# Sheet1.net
KiCad netlist of a schematic drawn in Altium Designer
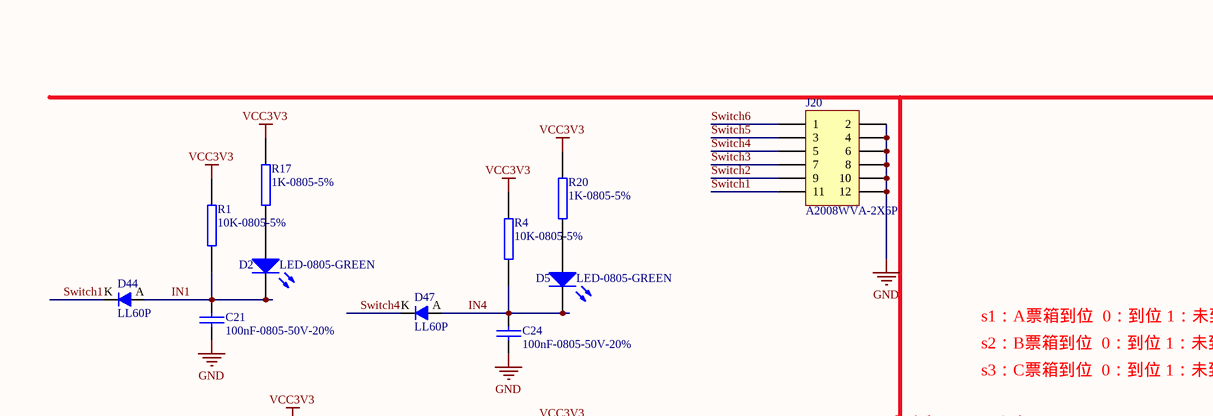
[diagram p0: Sheet1.SchDoc, top left]
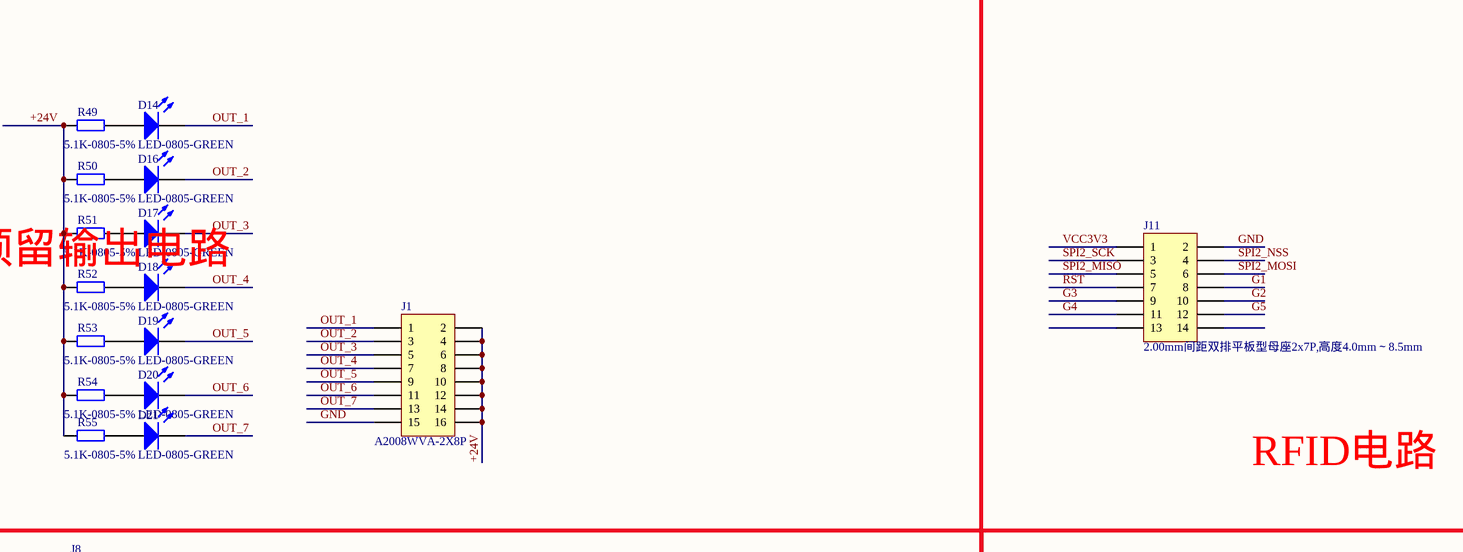
[diagram p1: Sheet1.SchDoc, top middle]
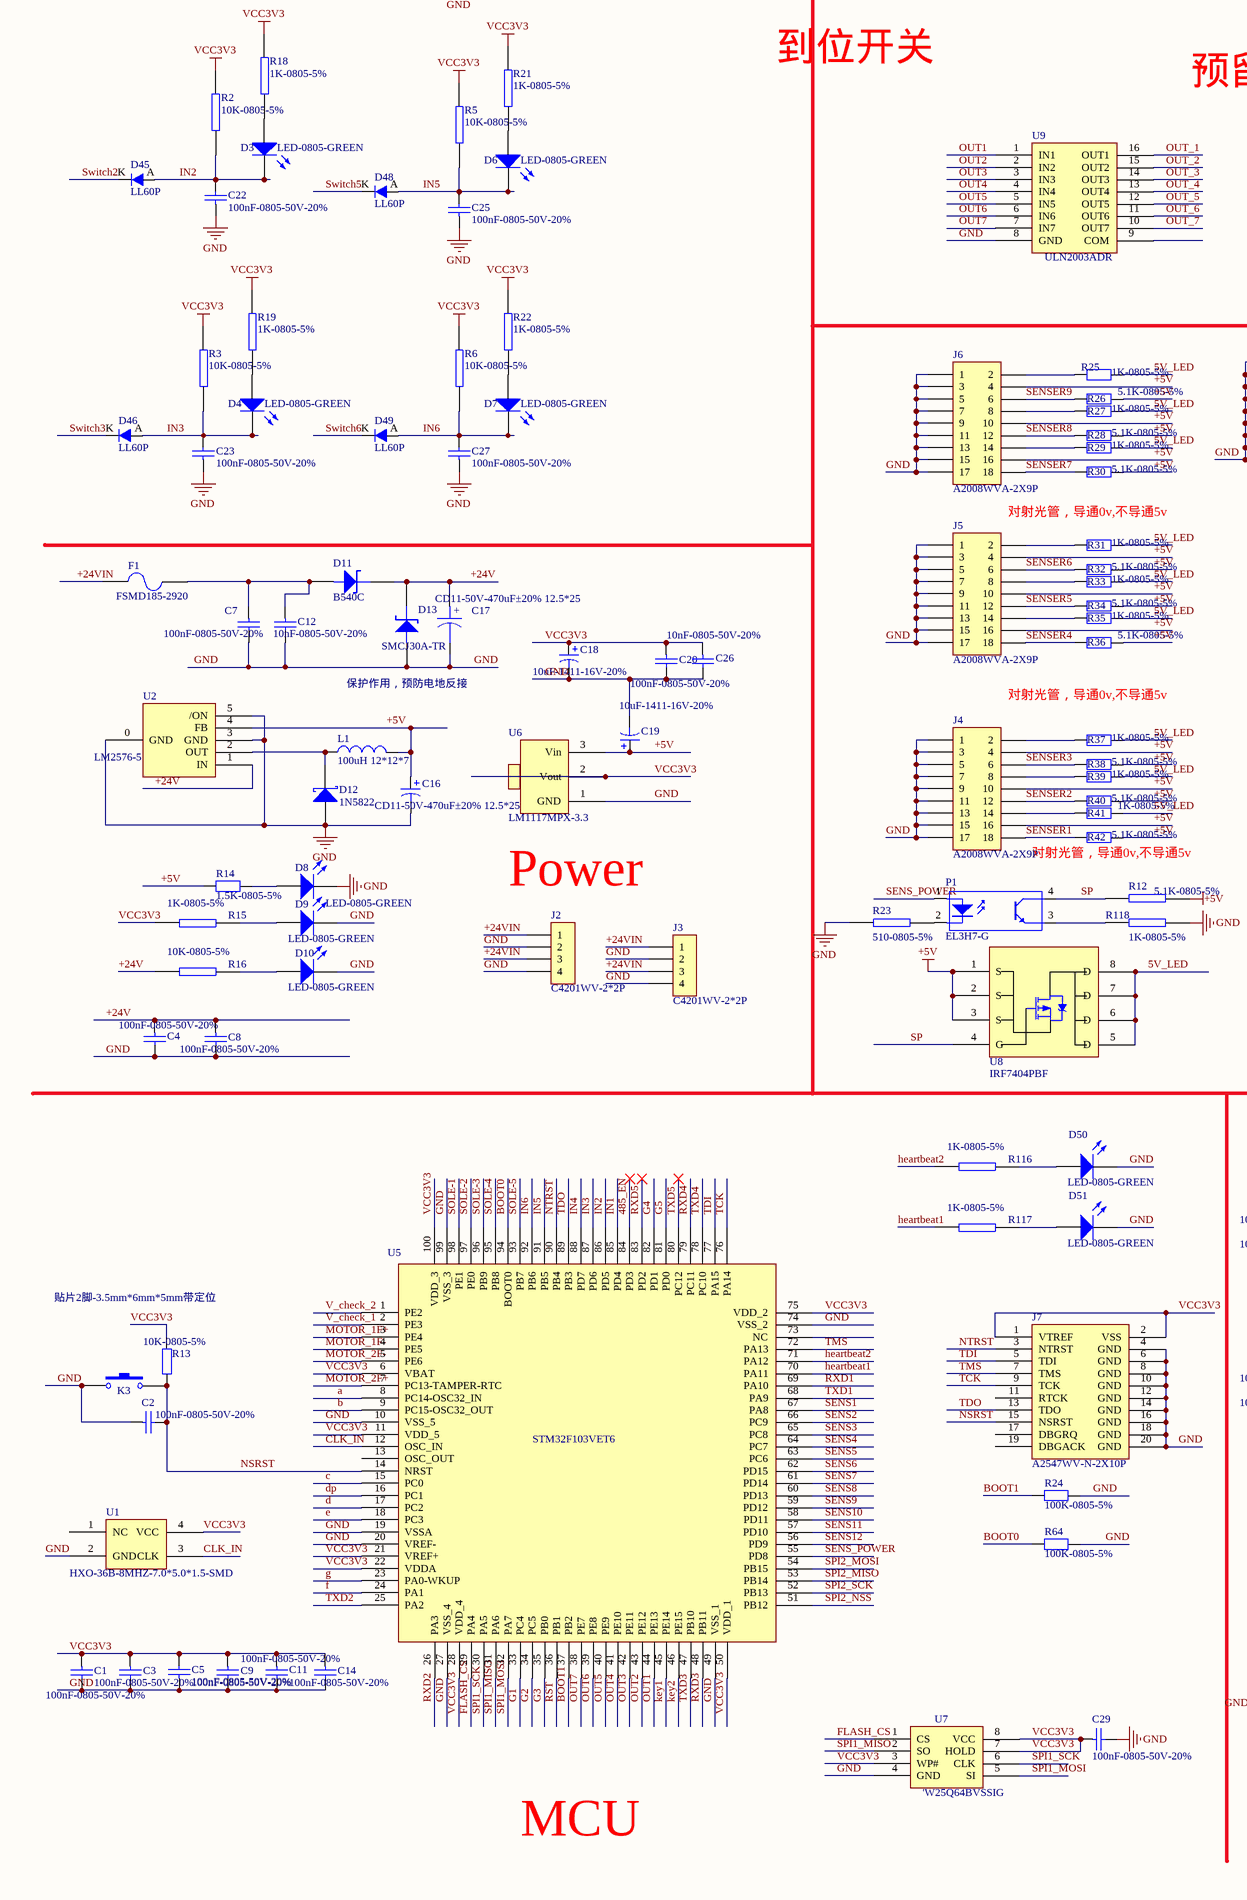
[diagram p2: Sheet1.SchDoc, bottom left]
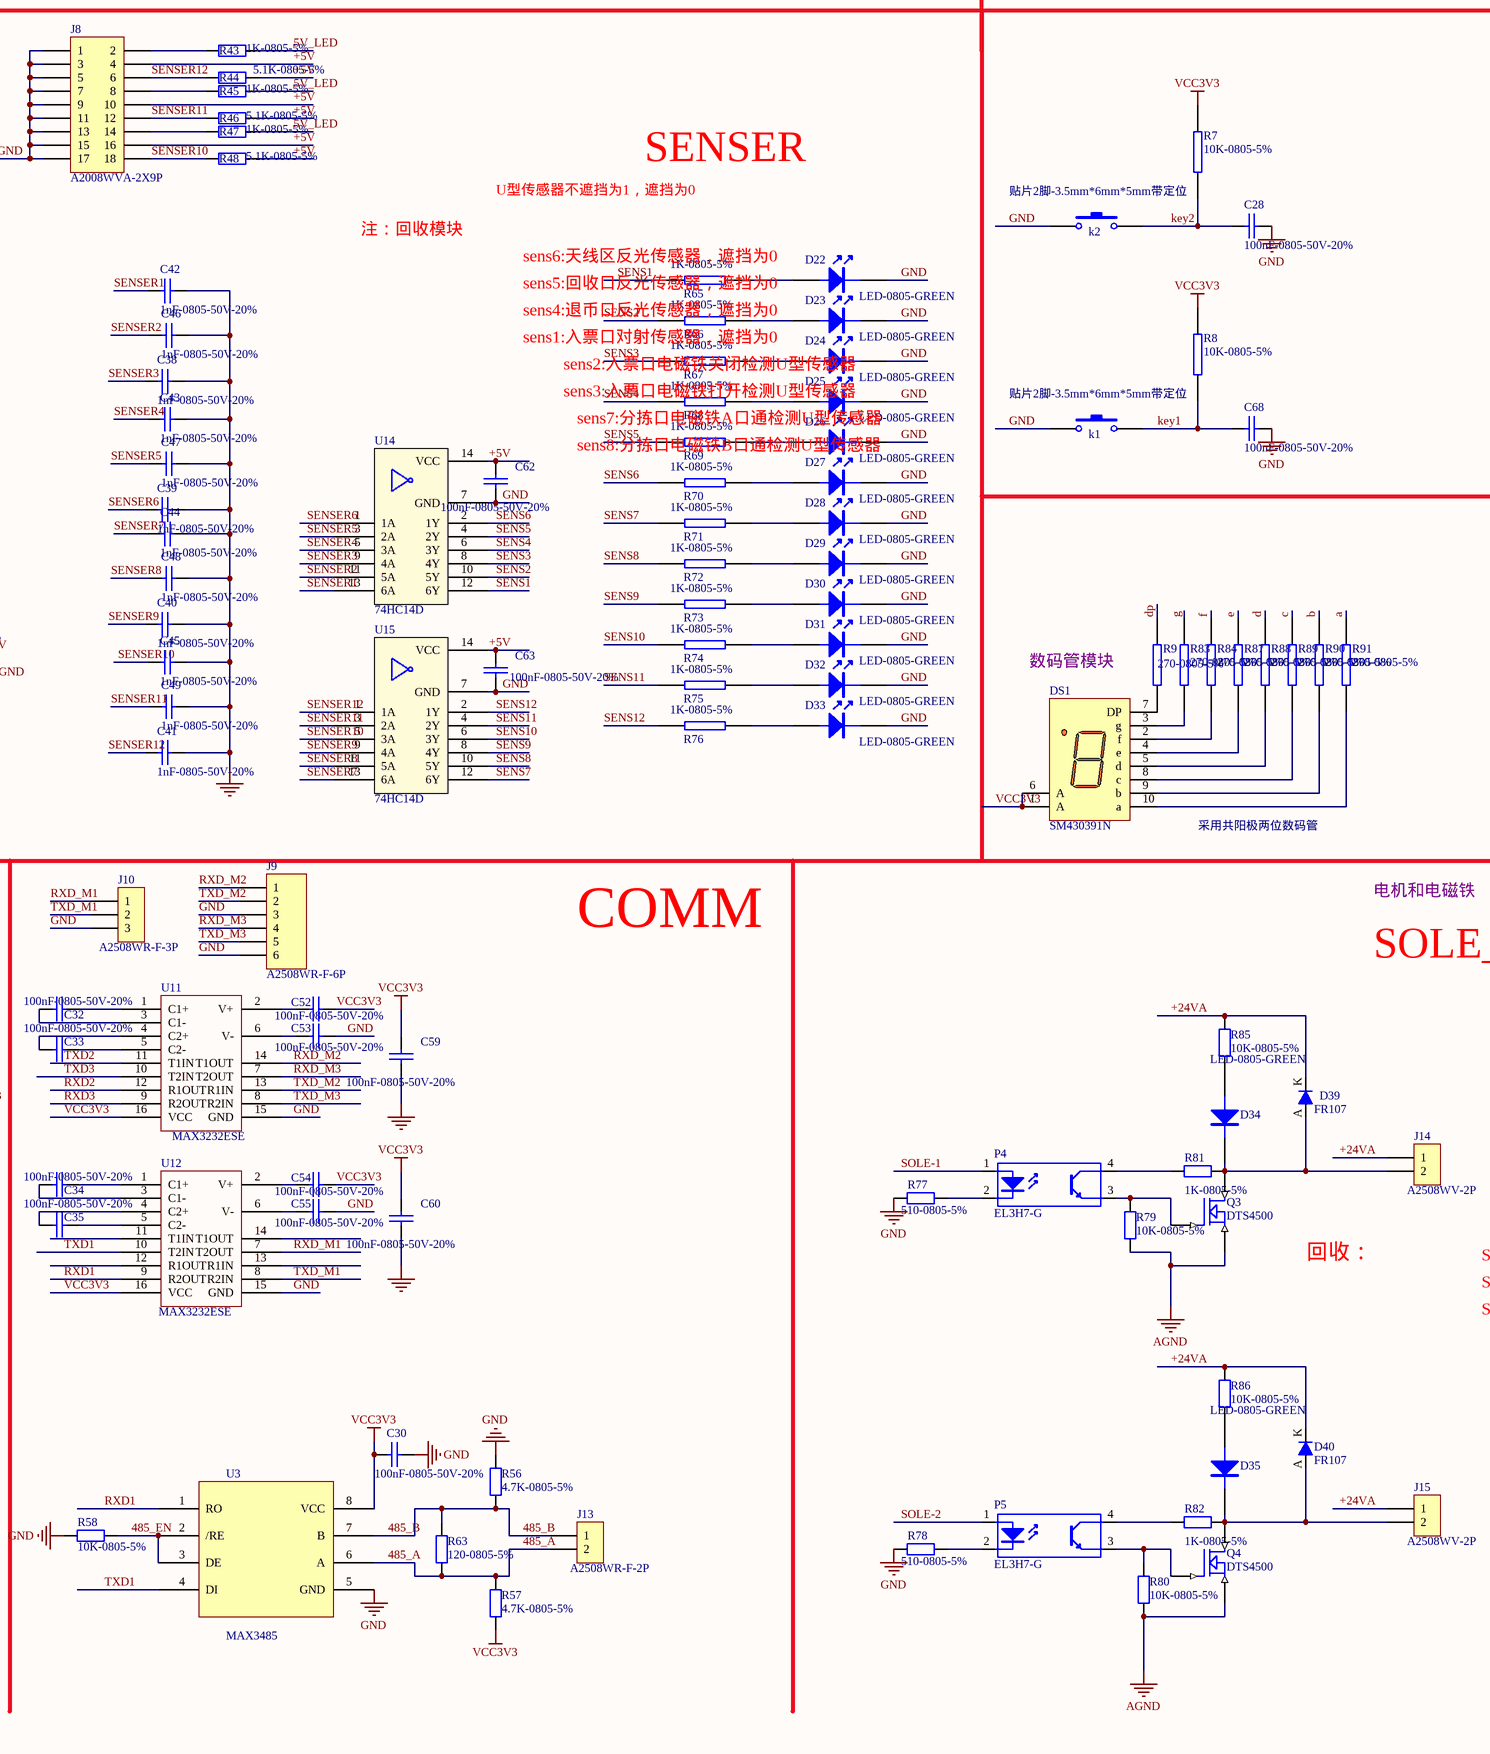
[diagram p3: Sheet1.SchDoc, bottom middle]
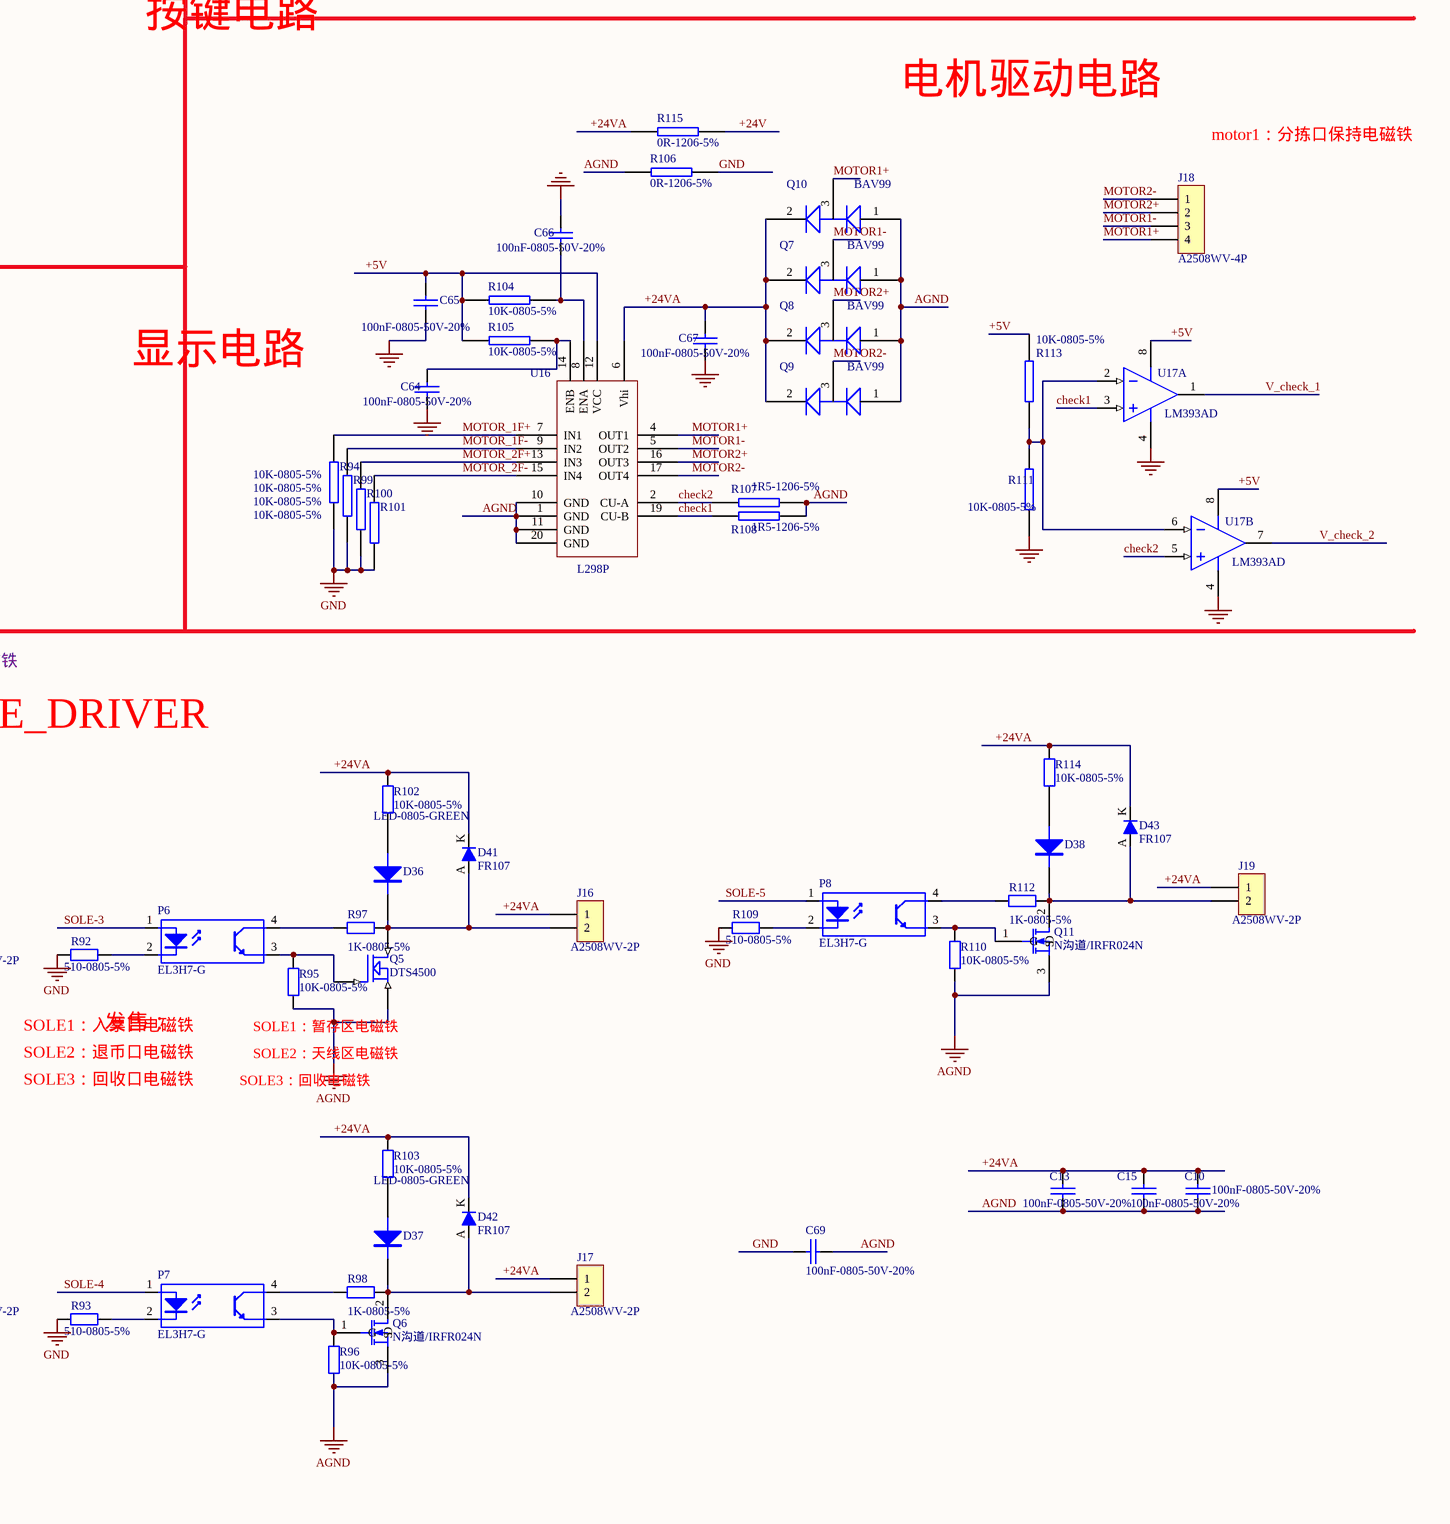
[diagram p4: Sheet1.SchDoc, bottom right]

(export (version "E")
  (design (tool "Eeschema 10.0.6"))
  (components
    (comp (ref "C1")
      (value "100nF-0805-50V-20%")
      (footprint "0805")
      (description "Capacitor")
      (libsource (lib "*") (part "CAP"))
    )
    (comp (ref "C2")
      (value "100nF-0805-50V-20%")
      (footprint "0805")
      (description "Capacitor")
      (libsource (lib "*") (part "CAP"))
    )
    (comp (ref "C3")
      (value "100nF-0805-50V-20%")
      (footprint "0805")
      (description "Capacitor")
      (libsource (lib "*") (part "CAP"))
    )
    (comp (ref "C4")
      (value "100nF-0805-50V-20%")
      (footprint "0805")
      (description "Capacitor")
      (libsource (lib "*") (part "CAP"))
    )
    (comp (ref "C5")
      (value "100nF-0805-50V-20%")
      (footprint "0805")
      (description "Capacitor")
      (libsource (lib "*") (part "CAP"))
    )
    (comp (ref "C7")
      (value "100nF-0805-50V-20%")
      (footprint "0805")
      (description "Capacitor")
      (libsource (lib "*") (part "CAP"))
    )
    (comp (ref "C8")
      (value "100nF-0805-50V-20%")
      (footprint "0805")
      (description "Capacitor")
      (libsource (lib "*") (part "CAP"))
    )
    (comp (ref "C9")
      (value "100nF-0805-50V-20%")
      (footprint "0805")
      (description "Capacitor")
      (libsource (lib "*") (part "CAP"))
    )
    (comp (ref "C10")
      (value "100nF-0805-50V-20%")
      (footprint "0805")
      (description "Capacitor")
      (libsource (lib "*") (part "CAP"))
    )
    (comp (ref "C11")
      (value "100nF-0805-50V-20%")
      (footprint "0805")
      (description "Capacitor")
      (libsource (lib "*") (part "CAP"))
    )
    (comp (ref "C12")
      (value "10nF-0805-50V-20%")
      (footprint "0805")
      (description "Capacitor")
      (libsource (lib "*") (part "CAP"))
    )
    (comp (ref "C13")
      (value "100nF-0805-50V-20%")
      (footprint "0805")
      (description "Capacitor")
      (libsource (lib "*") (part "CAP"))
    )
    (comp (ref "C14")
      (value "100nF-0805-50V-20%")
      (footprint "0805")
      (description "Capacitor")
      (libsource (lib "*") (part "CAP"))
    )
    (comp (ref "C15")
      (value "100nF-0805-50V-20%")
      (footprint "0805")
      (description "Capacitor")
      (libsource (lib "*") (part "CAP"))
    )
    (comp (ref "C16")
      (value "CD11-50V-470uF±20% 12.5*25")
      (footprint "RB.2/.4")
      (description "Polarized Capacitor (Radial)")
      (fields (field (name "PUBLISHER") "Altium Limited"))
      (libsource (lib "Miscellaneous Devices") (part "Cap Pol1"))
    )
    (comp (ref "C17")
      (value "CD11-50V-470uF±20% 12.5*25")
      (footprint "RB.2/.4")
      (description "Capacitor")
      (libsource (lib "*") (part "CAPACITOR POL"))
    )
    (comp (ref "C18")
      (value "10uF-1411-16V-20%")
      (footprint "1411-B")
      (description "Polarized Capacitor (Radial)")
      (fields (field (name "PUBLISHER") "Altium Limited"))
      (libsource (lib "Miscellaneous Devices") (part "Cap Pol1"))
    )
    (comp (ref "C19")
      (value "10uF-1411-16V-20%")
      (footprint "1411-B")
      (description "Polarized Capacitor (Radial)")
      (fields (field (name "PUBLISHER") "Altium Limited"))
      (libsource (lib "Miscellaneous Devices") (part "Cap Pol1"))
    )
    (comp (ref "C20")
      (value "100nF-0805-50V-20%")
      (footprint "0805")
      (description "Capacitor")
      (libsource (lib "*") (part "CAP"))
    )
    (comp (ref "C21")
      (value "100nF-0805-50V-20%")
      (footprint "0805")
      (description "Capacitor")
      (libsource (lib "*") (part "CAP"))
    )
    (comp (ref "C22")
      (value "100nF-0805-50V-20%")
      (footprint "0805")
      (description "Capacitor")
      (libsource (lib "*") (part "CAP"))
    )
    (comp (ref "C23")
      (value "100nF-0805-50V-20%")
      (footprint "0805")
      (description "Capacitor")
      (libsource (lib "*") (part "CAP"))
    )
    (comp (ref "C24")
      (value "100nF-0805-50V-20%")
      (footprint "0805")
      (description "Capacitor")
      (libsource (lib "*") (part "CAP"))
    )
    (comp (ref "C25")
      (value "100nF-0805-50V-20%")
      (footprint "0805")
      (description "Capacitor")
      (libsource (lib "*") (part "CAP"))
    )
    (comp (ref "C26")
      (value "10nF-0805-50V-20%")
      (footprint "0805")
      (description "Capacitor")
      (libsource (lib "*") (part "CAP"))
    )
    (comp (ref "C27")
      (value "100nF-0805-50V-20%")
      (footprint "0805")
      (description "Capacitor")
      (libsource (lib "*") (part "CAP"))
    )
    (comp (ref "C28")
      (value "100nF-0805-50V-20%")
      (footprint "0805")
      (description "Capacitor")
      (libsource (lib "*") (part "CAP"))
    )
    (comp (ref "C29")
      (value "100nF-0805-50V-20%")
      (footprint "0805")
      (description "Capacitor")
      (libsource (lib "*") (part "CAP"))
    )
    (comp (ref "C30")
      (value "100nF-0805-50V-20%")
      (footprint "0805")
      (description "Capacitor")
      (libsource (lib "*") (part "CAP"))
    )
    (comp (ref "C32")
      (value "100nF-0805-50V-20%")
      (footprint "0805")
      (description "Capacitor")
      (libsource (lib "") (part "CAP_1"))
    )
    (comp (ref "C33")
      (value "100nF-0805-50V-20%")
      (footprint "0805")
      (description "Capacitor")
      (libsource (lib "") (part "CAP_1"))
    )
    (comp (ref "C34")
      (value "100nF-0805-50V-20%")
      (footprint "0805")
      (description "Capacitor")
      (libsource (lib "") (part "CAP_1"))
    )
    (comp (ref "C35")
      (value "100nF-0805-50V-20%")
      (footprint "0805")
      (description "Capacitor")
      (libsource (lib "") (part "CAP_1"))
    )
    (comp (ref "C38")
      (value "1nF-0805-50V-20%")
      (footprint "0805")
      (description "Capacitor")
      (libsource (lib "*") (part "CAP"))
    )
    (comp (ref "C39")
      (value "1nF-0805-50V-20%")
      (footprint "0805")
      (description "Capacitor")
      (libsource (lib "*") (part "CAP"))
    )
    (comp (ref "C40")
      (value "1nF-0805-50V-20%")
      (footprint "0805")
      (description "Capacitor")
      (libsource (lib "*") (part "CAP"))
    )
    (comp (ref "C41")
      (value "1nF-0805-50V-20%")
      (footprint "0805")
      (description "Capacitor")
      (libsource (lib "*") (part "CAP"))
    )
    (comp (ref "C42")
      (value "1nF-0805-50V-20%")
      (footprint "0805")
      (description "Capacitor")
      (libsource (lib "*") (part "CAP"))
    )
    (comp (ref "C43")
      (value "1nF-0805-50V-20%")
      (footprint "0805")
      (description "Capacitor")
      (libsource (lib "*") (part "CAP"))
    )
    (comp (ref "C44")
      (value "1nF-0805-50V-20%")
      (footprint "0805")
      (description "Capacitor")
      (libsource (lib "*") (part "CAP"))
    )
    (comp (ref "C45")
      (value "1nF-0805-50V-20%")
      (footprint "0805")
      (description "Capacitor")
      (libsource (lib "*") (part "CAP"))
    )
    (comp (ref "C46")
      (value "1nF-0805-50V-20%")
      (footprint "0805")
      (description "Capacitor")
      (libsource (lib "*") (part "CAP"))
    )
    (comp (ref "C47")
      (value "1nF-0805-50V-20%")
      (footprint "0805")
      (description "Capacitor")
      (libsource (lib "*") (part "CAP"))
    )
    (comp (ref "C48")
      (value "1nF-0805-50V-20%")
      (footprint "0805")
      (description "Capacitor")
      (libsource (lib "*") (part "CAP"))
    )
    (comp (ref "C49")
      (value "1nF-0805-50V-20%")
      (footprint "0805")
      (description "Capacitor")
      (libsource (lib "*") (part "CAP"))
    )
    (comp (ref "C52")
      (value "100nF-0805-50V-20%")
      (footprint "0805")
      (description "Capacitor")
      (libsource (lib "") (part "CAP_1"))
    )
    (comp (ref "C53")
      (value "100nF-0805-50V-20%")
      (footprint "0805")
      (description "Capacitor")
      (libsource (lib "") (part "CAP_1"))
    )
    (comp (ref "C54")
      (value "100nF-0805-50V-20%")
      (footprint "0805")
      (description "Capacitor")
      (libsource (lib "") (part "CAP_1"))
    )
    (comp (ref "C55")
      (value "100nF-0805-50V-20%")
      (footprint "0805")
      (description "Capacitor")
      (libsource (lib "") (part "CAP_1"))
    )
    (comp (ref "C59")
      (value "100nF-0805-50V-20%")
      (footprint "0805")
      (description "Capacitor")
      (libsource (lib "*") (part "CAP"))
    )
    (comp (ref "C60")
      (value "100nF-0805-50V-20%")
      (footprint "0805")
      (description "Capacitor")
      (libsource (lib "*") (part "CAP"))
    )
    (comp (ref "C62")
      (value "100nF-0805-50V-20%")
      (footprint "0805")
      (description "Capacitor")
      (libsource (lib "*") (part "CAP"))
    )
    (comp (ref "C63")
      (value "100nF-0805-50V-20%")
      (footprint "0805")
      (description "Capacitor")
      (libsource (lib "*") (part "CAP"))
    )
    (comp (ref "C64")
      (value "100nF-0805-50V-20%")
      (footprint "0805")
      (description "Capacitor")
      (libsource (lib "*") (part "CAP"))
    )
    (comp (ref "C65")
      (value "100nF-0805-50V-20%")
      (footprint "0805")
      (description "Capacitor")
      (libsource (lib "*") (part "CAP"))
    )
    (comp (ref "C66")
      (value "100nF-0805-50V-20%")
      (footprint "0805")
      (description "Capacitor")
      (libsource (lib "*") (part "CAP"))
    )
    (comp (ref "C67")
      (value "100nF-0805-50V-20%")
      (footprint "0805")
      (description "Capacitor")
      (libsource (lib "*") (part "CAP"))
    )
    (comp (ref "C68")
      (value "100nF-0805-50V-20%")
      (footprint "0805")
      (description "Capacitor")
      (libsource (lib "*") (part "CAP"))
    )
    (comp (ref "C69")
      (value "100nF-0805-50V-20%")
      (footprint "0805")
      (description "Capacitor")
      (libsource (lib "*") (part "CAP"))
    )
    (comp (ref "D2")
      (value "LED-0805-GREEN")
      (footprint "LED-0805")
      (description "Typical INFRARED GaAs LED")
      (fields (field (name "PUBLISHER") "Altium Limited"))
      (libsource (lib "Miscellaneous Devices") (part "LED0"))
    )
    (comp (ref "D3")
      (value "LED-0805-GREEN")
      (footprint "LED-0805")
      (description "Typical INFRARED GaAs LED")
      (fields (field (name "PUBLISHER") "Altium Limited"))
      (libsource (lib "Miscellaneous Devices") (part "LED0"))
    )
    (comp (ref "D4")
      (value "LED-0805-GREEN")
      (footprint "LED-0805")
      (description "Typical INFRARED GaAs LED")
      (fields (field (name "PUBLISHER") "Altium Limited"))
      (libsource (lib "Miscellaneous Devices") (part "LED0"))
    )
    (comp (ref "D5")
      (value "LED-0805-GREEN")
      (footprint "LED-0805")
      (description "Typical INFRARED GaAs LED")
      (fields (field (name "PUBLISHER") "Altium Limited"))
      (libsource (lib "Miscellaneous Devices") (part "LED0"))
    )
    (comp (ref "D6")
      (value "LED-0805-GREEN")
      (footprint "LED-0805")
      (description "Typical INFRARED GaAs LED")
      (fields (field (name "PUBLISHER") "Altium Limited"))
      (libsource (lib "Miscellaneous Devices") (part "LED0"))
    )
    (comp (ref "D7")
      (value "LED-0805-GREEN")
      (footprint "LED-0805")
      (description "Typical INFRARED GaAs LED")
      (fields (field (name "PUBLISHER") "Altium Limited"))
      (libsource (lib "Miscellaneous Devices") (part "LED0"))
    )
    (comp (ref "D8")
      (value "LED-0805-GREEN")
      (footprint "LED-0805")
      (description "Typical INFRARED GaAs LED")
      (fields (field (name "PUBLISHER") "Altium Limited"))
      (libsource (lib "Miscellaneous Devices") (part "LED0"))
    )
    (comp (ref "D9")
      (value "LED-0805-GREEN")
      (footprint "LED-0805")
      (description "Typical INFRARED GaAs LED")
      (fields (field (name "PUBLISHER") "Altium Limited"))
      (libsource (lib "Miscellaneous Devices") (part "LED0"))
    )
    (comp (ref "D10")
      (value "LED-0805-GREEN")
      (footprint "LED-0805")
      (description "Typical INFRARED GaAs LED")
      (fields (field (name "PUBLISHER") "Altium Limited"))
      (libsource (lib "Miscellaneous Devices") (part "LED0"))
    )
    (comp (ref "D11")
      (value "B540C")
      (footprint "SMC")
      (description "Zener Diode")
      (libsource (lib "*") (part "ZENER2"))
    )
    (comp (ref "D12")
      (value "1N5822")
      (footprint "IN5822 SMT")
      (description "Schottky Diode")
      (fields (field (name "PUBLISHER") "Altium Limited"))
      (libsource (lib "Miscellaneous Devices") (part "D Schottky"))
    )
    (comp (ref "D13")
      (value "SMCJ30A-TR")
      (footprint "SMC")
      (description "Zener Diode")
      (libsource (lib "*") (part "ZENER2"))
    )
    (comp (ref "D14")
      (value "LED-0805-GREEN")
      (footprint "LED-0805")
      (description "Typical INFRARED GaAs LED")
      (fields (field (name "PUBLISHER") "Altium Limited"))
      (libsource (lib "Miscellaneous Devices") (part "LED0"))
    )
    (comp (ref "D16")
      (value "LED-0805-GREEN")
      (footprint "LED-0805")
      (description "Typical INFRARED GaAs LED")
      (fields (field (name "PUBLISHER") "Altium Limited"))
      (libsource (lib "Miscellaneous Devices") (part "LED0"))
    )
    (comp (ref "D17")
      (value "LED-0805-GREEN")
      (footprint "LED-0805")
      (description "Typical INFRARED GaAs LED")
      (fields (field (name "PUBLISHER") "Altium Limited"))
      (libsource (lib "Miscellaneous Devices") (part "LED0"))
    )
    (comp (ref "D18")
      (value "LED-0805-GREEN")
      (footprint "LED-0805")
      (description "Typical INFRARED GaAs LED")
      (fields (field (name "PUBLISHER") "Altium Limited"))
      (libsource (lib "Miscellaneous Devices") (part "LED0"))
    )
    (comp (ref "D19")
      (value "LED-0805-GREEN")
      (footprint "LED-0805")
      (description "Typical INFRARED GaAs LED")
      (fields (field (name "PUBLISHER") "Altium Limited"))
      (libsource (lib "Miscellaneous Devices") (part "LED0"))
    )
    (comp (ref "D20")
      (value "LED-0805-GREEN")
      (footprint "LED-0805")
      (description "Typical INFRARED GaAs LED")
      (fields (field (name "PUBLISHER") "Altium Limited"))
      (libsource (lib "Miscellaneous Devices") (part "LED0"))
    )
    (comp (ref "D21")
      (value "LED-0805-GREEN")
      (footprint "LED-0805")
      (description "Typical INFRARED GaAs LED")
      (fields (field (name "PUBLISHER") "Altium Limited"))
      (libsource (lib "Miscellaneous Devices") (part "LED0"))
    )
    (comp (ref "D22") (value "LED-0805-GREEN") (footprint "LED-0805") (libsource (lib "*") (part "LED")))
    (comp (ref "D23") (value "LED-0805-GREEN") (footprint "LED-0805") (libsource (lib "*") (part "LED")))
    (comp (ref "D24") (value "LED-0805-GREEN") (footprint "LED-0805") (libsource (lib "*") (part "LED")))
    (comp (ref "D25") (value "LED-0805-GREEN") (footprint "LED-0805") (libsource (lib "*") (part "LED")))
    (comp (ref "D26") (value "LED-0805-GREEN") (footprint "LED-0805") (libsource (lib "*") (part "LED")))
    (comp (ref "D27") (value "LED-0805-GREEN") (footprint "LED-0805") (libsource (lib "*") (part "LED")))
    (comp (ref "D28") (value "LED-0805-GREEN") (footprint "LED-0805") (libsource (lib "*") (part "LED")))
    (comp (ref "D29") (value "LED-0805-GREEN") (footprint "LED-0805") (libsource (lib "*") (part "LED")))
    (comp (ref "D30") (value "LED-0805-GREEN") (footprint "LED-0805") (libsource (lib "*") (part "LED")))
    (comp (ref "D31") (value "LED-0805-GREEN") (footprint "LED-0805") (libsource (lib "*") (part "LED")))
    (comp (ref "D32") (value "LED-0805-GREEN") (footprint "LED-0805") (libsource (lib "*") (part "LED")))
    (comp (ref "D33") (value "LED-0805-GREEN") (footprint "LED-0805") (libsource (lib "*") (part "LED")))
    (comp (ref "D34")
      (value "LED-0805-GREEN")
      (footprint "LED-0805")
      (description "Diode")
      (libsource (lib "*") (part "DIODE"))
    )
    (comp (ref "D35")
      (value "LED-0805-GREEN")
      (footprint "LED-0805")
      (description "Diode")
      (libsource (lib "*") (part "DIODE"))
    )
    (comp (ref "D36")
      (value "LED-0805-GREEN")
      (footprint "LED-0805")
      (description "Diode")
      (libsource (lib "*") (part "DIODE"))
    )
    (comp (ref "D37")
      (value "LED-0805-GREEN")
      (footprint "LED-0805")
      (description "Diode")
      (libsource (lib "*") (part "DIODE"))
    )
    (comp (ref "D38")
      (value "LED-0805-GREEN")
      (footprint "LED-0805")
      (description "Diode")
      (libsource (lib "*") (part "DIODE"))
    )
    (comp (ref "D39")
      (value "FR107")
      (footprint "DO-214AC")
      (libsource (lib "T-SZLG-MCB-16-0247-PN-37990042-SZLG-Hopper-01控制板") (part "1N4148"))
    )
    (comp (ref "D40")
      (value "FR107")
      (footprint "DO-214AC")
      (libsource (lib "T-SZLG-MCB-16-0247-PN-37990042-SZLG-Hopper-01控制板") (part "1N4148"))
    )
    (comp (ref "D41")
      (value "FR107")
      (footprint "DO-214AC")
      (libsource (lib "T-SZLG-MCB-16-0247-PN-37990042-SZLG-Hopper-01控制板") (part "1N4148"))
    )
    (comp (ref "D42")
      (value "FR107")
      (footprint "DO-214AC")
      (libsource (lib "T-SZLG-MCB-16-0247-PN-37990042-SZLG-Hopper-01控制板") (part "1N4148"))
    )
    (comp (ref "D43")
      (value "FR107")
      (footprint "DO-214AC")
      (libsource (lib "T-SZLG-MCB-16-0247-PN-37990042-SZLG-Hopper-01控制板") (part "1N4148"))
    )
    (comp (ref "D44")
      (value "LL60P")
      (footprint "PCB22:DIODE")
      (libsource (lib "T-SZLG-MCB-16-0247-PN-37990042-SZLG-Hopper-01控制板") (part "1N4148"))
    )
    (comp (ref "D45")
      (value "LL60P")
      (footprint "DIODE")
      (libsource (lib "T-SZLG-MCB-16-0247-PN-37990042-SZLG-Hopper-01控制板") (part "1N4148"))
    )
    (comp (ref "D46")
      (value "LL60P")
      (footprint "DIODE")
      (libsource (lib "T-SZLG-MCB-16-0247-PN-37990042-SZLG-Hopper-01控制板") (part "1N4148"))
    )
    (comp (ref "D47")
      (value "LL60P")
      (footprint "DIODE")
      (libsource (lib "T-SZLG-MCB-16-0247-PN-37990042-SZLG-Hopper-01控制板") (part "1N4148"))
    )
    (comp (ref "D48")
      (value "LL60P")
      (footprint "DIODE")
      (libsource (lib "T-SZLG-MCB-16-0247-PN-37990042-SZLG-Hopper-01控制板") (part "1N4148"))
    )
    (comp (ref "D49")
      (value "LL60P")
      (footprint "DIODE")
      (libsource (lib "T-SZLG-MCB-16-0247-PN-37990042-SZLG-Hopper-01控制板") (part "1N4148"))
    )
    (comp (ref "D50")
      (value "LED-0805-GREEN")
      (footprint "LED-0805")
      (description "Typical INFRARED GaAs LED")
      (fields (field (name "PUBLISHER") "Altium Limited"))
      (libsource (lib "Miscellaneous Devices") (part "LED0"))
    )
    (comp (ref "D51")
      (value "LED-0805-GREEN")
      (footprint "LED-0805")
      (description "Typical INFRARED GaAs LED")
      (fields (field (name "PUBLISHER") "Altium Limited"))
      (libsource (lib "Miscellaneous Devices") (part "LED0"))
    )
    (comp (ref "DS1")
      (value "SM430391N")
      (footprint "LEDDIP-10")
      (description "7.62 mm Black Surface Orange 7-Segment Display: CA, RH DP")
      (fields (field (name "PUBLISHER") "Altium Limited"))
      (libsource (lib "*") (part "Dpy Amber-CA"))
    )
    (comp (ref "F1")
      (value "FSMD185-2920")
      (footprint "2920")
      (description "Fuse")
      (libsource (lib "*") (part "FUSE2"))
    )
    (comp (ref "J1")
      (value "A2008WVA-2X8P")
      (footprint "PCB12:A2008WVA-2X8P")
      (description "Header, 8-Pin, Dual row")
      (fields (field (name "PUBLISHER") "Altium Limited"))
      (libsource (lib "Miscellaneous Connectors") (part "Header 8X2"))
    )
    (comp (ref "J2")
      (value "C4201WV-2*2P")
      (footprint "MX4 .2- 2*2P-180")
      (description "Connector")
      (libsource (lib "*") (part "CON4"))
    )
    (comp (ref "J3")
      (value "C4201WV-2*2P")
      (footprint "PCB1:MX4 .2- 2*2P-180")
      (description "Connector")
      (libsource (lib "*") (part "CON4"))
    )
    (comp (ref "J4")
      (value "A2008WVA-2X9P")
      (footprint "PCB12:A2008WVA-2X9P")
      (description "Header, 9-Pin, Dual row")
      (fields (field (name "PUBLISHER") "Altium Limited"))
      (libsource (lib "Miscellaneous Connectors") (part "Header 9X2"))
    )
    (comp (ref "J5")
      (value "A2008WVA-2X9P")
      (footprint "PCB12:A2008WVA-2X9P")
      (description "Header, 9-Pin, Dual row")
      (fields (field (name "PUBLISHER") "Altium Limited"))
      (libsource (lib "Miscellaneous Connectors") (part "Header 9X2"))
    )
    (comp (ref "J6")
      (value "A2008WVA-2X9P")
      (footprint "PCB12:A2008WVA-2X9P")
      (description "Header, 9-Pin, Dual row")
      (fields (field (name "PUBLISHER") "Altium Limited"))
      (libsource (lib "Miscellaneous Connectors") (part "Header 9X2"))
    )
    (comp (ref "J7") (value "A2547WV-N-2X10P") (footprint "JTAG_20") (libsource (lib "STM32") (part "JTAG")))
    (comp (ref "J8")
      (value "A2008WVA-2X9P")
      (footprint "PCB12:A2008WVA-2X9P")
      (description "Header, 9-Pin, Dual row")
      (fields (field (name "PUBLISHER") "Altium Limited"))
      (libsource (lib "Miscellaneous Connectors") (part "Header 9X2"))
    )
    (comp (ref "J9")
      (value "A2508WR-F-6P")
      (footprint "PCB1:2.5-6P  90 JXT")
      (description "Header, 6-Pin")
      (fields (field (name "PUBLISHER") "Altium Limited"))
      (libsource (lib "Miscellaneous Connectors") (part "Header 6"))
    )
    (comp (ref "J10")
      (value "A2508WR-F-3P")
      (footprint "PCB1:2.5-3P  90 JXT")
      (description "Connector")
      (libsource (lib "*") (part "CON3"))
    )
    (comp (ref "J11")
      (value "2.00mm间距双排平板型母座2x7P,高度4.0mm～8.5mm")
      (footprint "PCB1:IDC14-2.0-F")
      (description "Header, 7-Pin, Dual row, Right Angle")
      (fields (field (name "PUBLISHER") "Altium Limited"))
      (libsource (lib "Miscellaneous Connectors") (part "Header 7X2H"))
    )
    (comp (ref "J13")
      (value "A2508WR-F-2P")
      (footprint "2.5-2P  90 JXT")
      (libsource (lib "元件库") (part "CON2"))
    )
    (comp (ref "J14")
      (value "A2508WV-2P")
      (footprint "2.5-2P  180 JXT")
      (libsource (lib "元件库") (part "CON2"))
    )
    (comp (ref "J15")
      (value "A2508WV-2P")
      (footprint "2.5-2P  180 JXT")
      (libsource (lib "元件库") (part "CON2"))
    )
    (comp (ref "J16")
      (value "A2508WV-2P")
      (footprint "2.5-2P  180 JXT")
      (libsource (lib "元件库") (part "CON2"))
    )
    (comp (ref "J17")
      (value "A2508WV-2P")
      (footprint "2.5-2P  180 JXT")
      (libsource (lib "元件库") (part "CON2"))
    )
    (comp (ref "J18")
      (value "A2508WV-4P")
      (footprint "W143-4")
      (description "Connector")
      (libsource (lib "*") (part "CON4"))
    )
    (comp (ref "J19")
      (value "A2508WV-2P")
      (footprint "2.5-2P  180 JXT")
      (libsource (lib "元件库") (part "CON2"))
    )
    (comp (ref "J20")
      (value "A2008WVA-2X6P")
      (footprint "PCB12:A2008WVA-2X6P")
      (description "Header, 6-Pin, Dual row")
      (fields (field (name "PUBLISHER") "Altium Limited"))
      (libsource (lib "Miscellaneous Connectors") (part "Header 6X2"))
    )
    (comp (ref "k1")
      (value "贴片2脚-3.5mm*6mm*5mm带定位")
      (footprint "BUTTON2")
      (description "Switch")
      (libsource (lib "SilvestStandardSchLib") (part "Switch"))
    )
    (comp (ref "k2")
      (value "贴片2脚-3.5mm*6mm*5mm带定位")
      (footprint "BUTTON2")
      (description "Switch")
      (libsource (lib "SilvestStandardSchLib") (part "Switch"))
    )
    (comp (ref "K3")
      (value "贴片2脚-3.5mm*6mm*5mm带定位")
      (footprint "BUTTON2")
      (description "Switch")
      (libsource (lib "SilvestStandardSchLib") (part "Switch"))
    )
    (comp (ref "L1")
      (value "100uH 12*12*7")
      (footprint "Inductor SMT7")
      (description "Inductor")
      (fields (field (name "PUBLISHER") "Altium Limited"))
      (libsource (lib "Miscellaneous Devices") (part "Inductor"))
    )
    (comp (ref "P1")
      (value "EL3H7-G")
      (footprint "SSOP4")
      (description "OpticalCoupler")
      (libsource (lib "SilvestStandardSchLib") (part "OpticalCoupler"))
    )
    (comp (ref "P4")
      (value "EL3H7-G")
      (footprint "SSOP4")
      (description "OpticalCoupler")
      (libsource (lib "SilvestStandardSchLib") (part "OpticalCoupler"))
    )
    (comp (ref "P5")
      (value "EL3H7-G")
      (footprint "SSOP4")
      (description "OpticalCoupler")
      (libsource (lib "SilvestStandardSchLib") (part "OpticalCoupler"))
    )
    (comp (ref "P6")
      (value "EL3H7-G")
      (footprint "SSOP4")
      (description "OpticalCoupler")
      (libsource (lib "SilvestStandardSchLib") (part "OpticalCoupler"))
    )
    (comp (ref "P7")
      (value "EL3H7-G")
      (footprint "SSOP4")
      (description "OpticalCoupler")
      (libsource (lib "SilvestStandardSchLib") (part "OpticalCoupler"))
    )
    (comp (ref "P8")
      (value "EL3H7-G")
      (footprint "SSOP4")
      (description "OpticalCoupler")
      (libsource (lib "SilvestStandardSchLib") (part "OpticalCoupler"))
    )
    (comp (ref "Q3") (value "DTS4500") (footprint "SOT-23") (libsource (lib "*") (part "MOSFET N")))
    (comp (ref "Q4") (value "DTS4500") (footprint "SOT-23") (libsource (lib "*") (part "MOSFET N")))
    (comp (ref "Q5") (value "DTS4500") (footprint "SOT-23") (libsource (lib "*") (part "MOSFET N")))
    (comp (ref "Q6")
      (value "N沟道/IRFR024N")
      (footprint "TO-252AA")
      (description "N-Channel MOSFET")
      (fields (field (name "PUBLISHER") "Altium Limited"))
      (libsource (lib "T-SZLG-MCB-16-0247-PN-37990042-SZLG-Hopper-01控制板") (part "MOSFET-N"))
    )
    (comp (ref "Q7") (value "BAV99") (footprint "SOT-23") (libsource (lib "*") (part "BAV99")))
    (comp (ref "Q8") (value "BAV99") (footprint "SOT-23") (libsource (lib "*") (part "BAV99")))
    (comp (ref "Q9") (value "BAV99") (footprint "SOT-23") (libsource (lib "*") (part "BAV99")))
    (comp (ref "Q10") (value "BAV99") (footprint "SOT-23") (libsource (lib "*") (part "BAV99")))
    (comp (ref "Q11")
      (value "N沟道/IRFR024N")
      (footprint "TO-252AA")
      (description "N-Channel MOSFET")
      (fields (field (name "PUBLISHER") "Altium Limited"))
      (libsource (lib "T-SZLG-MCB-16-0247-PN-37990042-SZLG-Hopper-01控制板") (part "MOSFET-N"))
    )
    (comp (ref "R1") (value "10K-0805-5%") (footprint "0805") (libsource (lib "*") (part "RES2")))
    (comp (ref "R2") (value "10K-0805-5%") (footprint "0805") (libsource (lib "*") (part "RES2")))
    (comp (ref "R3") (value "10K-0805-5%") (footprint "0805") (libsource (lib "*") (part "RES2")))
    (comp (ref "R4") (value "10K-0805-5%") (footprint "0805") (libsource (lib "*") (part "RES2")))
    (comp (ref "R5") (value "10K-0805-5%") (footprint "0805") (libsource (lib "*") (part "RES2")))
    (comp (ref "R6") (value "10K-0805-5%") (footprint "0805") (libsource (lib "*") (part "RES2")))
    (comp (ref "R7") (value "10K-0805-5%") (footprint "0805") (libsource (lib "*") (part "RES2")))
    (comp (ref "R8") (value "10K-0805-5%") (footprint "0805") (libsource (lib "*") (part "RES2")))
    (comp (ref "R9") (value "270-0805-5%") (footprint "0805") (libsource (lib "*") (part "RES2")))
    (comp (ref "R12") (value "5.1K-0805-5%") (footprint "0805") (libsource (lib "*") (part "RES2")))
    (comp (ref "R13")
      (value "10K-0805-5%")
      (footprint "0805")
      (description "Resistor")
      (fields (field (name "PUBLISHER") "Altium Limited"))
      (libsource (lib "") (part "Res2_3"))
    )
    (comp (ref "R14")
      (value "1.5K-0805-5%")
      (footprint "0805")
      (description "Resistor")
      (fields (field (name "PUBLISHER") "Altium Limited"))
      (libsource (lib "") (part "Res2_2"))
    )
    (comp (ref "R15") (value "1K-0805-5%") (footprint "0805") (libsource (lib "") (part "RES2_1")))
    (comp (ref "R16") (value "10K-0805-5%") (footprint "0805") (libsource (lib "") (part "RES2_1")))
    (comp (ref "R17") (value "1K-0805-5%") (footprint "0805") (libsource (lib "*") (part "RES2")))
    (comp (ref "R18") (value "1K-0805-5%") (footprint "0805") (libsource (lib "*") (part "RES2")))
    (comp (ref "R19") (value "1K-0805-5%") (footprint "0805") (libsource (lib "*") (part "RES2")))
    (comp (ref "R20") (value "1K-0805-5%") (footprint "0805") (libsource (lib "*") (part "RES2")))
    (comp (ref "R21") (value "1K-0805-5%") (footprint "0805") (libsource (lib "*") (part "RES2")))
    (comp (ref "R22") (value "1K-0805-5%") (footprint "0805") (libsource (lib "*") (part "RES2")))
    (comp (ref "R23") (value "510-0805-5%") (footprint "0805") (libsource (lib "*") (part "RES2")))
    (comp (ref "R24")
      (value "100K-0805-5%")
      (footprint "0805")
      (description "Resistor")
      (fields (field (name "PUBLISHER") "Altium Limited"))
      (libsource (lib "Miscellaneous Devices") (part "Res2"))
    )
    (comp (ref "R25")
      (value "1K-0805-5%")
      (footprint "0805")
      (description "Resistor")
      (fields (field (name "PUBLISHER") "Altium Limited"))
      (libsource (lib "*") (part "Res2"))
    )
    (comp (ref "R26")
      (value "5.1K-0805-5%")
      (footprint "0805")
      (description "Resistor")
      (fields (field (name "PUBLISHER") "Altium Limited"))
      (libsource (lib "*") (part "Res2"))
    )
    (comp (ref "R27")
      (value "1K-0805-5%")
      (footprint "0805")
      (description "Resistor")
      (fields (field (name "PUBLISHER") "Altium Limited"))
      (libsource (lib "*") (part "Res2"))
    )
    (comp (ref "R28")
      (value "5.1K-0805-5%")
      (footprint "0805")
      (description "Resistor")
      (fields (field (name "PUBLISHER") "Altium Limited"))
      (libsource (lib "*") (part "Res2"))
    )
    (comp (ref "R29")
      (value "1K-0805-5%")
      (footprint "0805")
      (description "Resistor")
      (fields (field (name "PUBLISHER") "Altium Limited"))
      (libsource (lib "*") (part "Res2"))
    )
    (comp (ref "R30")
      (value "5.1K-0805-5%")
      (footprint "0805")
      (description "Resistor")
      (fields (field (name "PUBLISHER") "Altium Limited"))
      (libsource (lib "*") (part "Res2"))
    )
    (comp (ref "R31")
      (value "1K-0805-5%")
      (footprint "0805")
      (description "Resistor")
      (fields (field (name "PUBLISHER") "Altium Limited"))
      (libsource (lib "*") (part "Res2"))
    )
    (comp (ref "R32")
      (value "5.1K-0805-5%")
      (footprint "0805")
      (description "Resistor")
      (fields (field (name "PUBLISHER") "Altium Limited"))
      (libsource (lib "*") (part "Res2"))
    )
    (comp (ref "R33")
      (value "1K-0805-5%")
      (footprint "0805")
      (description "Resistor")
      (fields (field (name "PUBLISHER") "Altium Limited"))
      (libsource (lib "*") (part "Res2"))
    )
    (comp (ref "R34")
      (value "5.1K-0805-5%")
      (footprint "0805")
      (description "Resistor")
      (fields (field (name "PUBLISHER") "Altium Limited"))
      (libsource (lib "*") (part "Res2"))
    )
    (comp (ref "R35")
      (value "1K-0805-5%")
      (footprint "0805")
      (description "Resistor")
      (fields (field (name "PUBLISHER") "Altium Limited"))
      (libsource (lib "*") (part "Res2"))
    )
    (comp (ref "R36")
      (value "5.1K-0805-5%")
      (footprint "0805")
      (description "Resistor")
      (fields (field (name "PUBLISHER") "Altium Limited"))
      (libsource (lib "*") (part "Res2"))
    )
    (comp (ref "R37")
      (value "1K-0805-5%")
      (footprint "0805")
      (description "Resistor")
      (fields (field (name "PUBLISHER") "Altium Limited"))
      (libsource (lib "*") (part "Res2"))
    )
    (comp (ref "R38")
      (value "5.1K-0805-5%")
      (footprint "0805")
      (description "Resistor")
      (fields (field (name "PUBLISHER") "Altium Limited"))
      (libsource (lib "*") (part "Res2"))
    )
    (comp (ref "R39")
      (value "1K-0805-5%")
      (footprint "0805")
      (description "Resistor")
      (fields (field (name "PUBLISHER") "Altium Limited"))
      (libsource (lib "*") (part "Res2"))
    )
    (comp (ref "R40")
      (value "5.1K-0805-5%")
      (footprint "0805")
      (description "Resistor")
      (fields (field (name "PUBLISHER") "Altium Limited"))
      (libsource (lib "*") (part "Res2"))
    )
    (comp (ref "R41")
      (value "1K-0805-5%")
      (footprint "0805")
      (description "Resistor")
      (fields (field (name "PUBLISHER") "Altium Limited"))
      (libsource (lib "*") (part "Res2"))
    )
    (comp (ref "R42")
      (value "5.1K-0805-5%")
      (footprint "0805")
      (description "Resistor")
      (fields (field (name "PUBLISHER") "Altium Limited"))
      (libsource (lib "*") (part "Res2"))
    )
    (comp (ref "R43")
      (value "1K-0805-5%")
      (footprint "0805")
      (description "Resistor")
      (fields (field (name "PUBLISHER") "Altium Limited"))
      (libsource (lib "*") (part "Res2"))
    )
    (comp (ref "R44")
      (value "5.1K-0805-5%")
      (footprint "0805")
      (description "Resistor")
      (fields (field (name "PUBLISHER") "Altium Limited"))
      (libsource (lib "*") (part "Res2"))
    )
    (comp (ref "R45")
      (value "1K-0805-5%")
      (footprint "0805")
      (description "Resistor")
      (fields (field (name "PUBLISHER") "Altium Limited"))
      (libsource (lib "*") (part "Res2"))
    )
    (comp (ref "R46")
      (value "5.1K-0805-5%")
      (footprint "0805")
      (description "Resistor")
      (fields (field (name "PUBLISHER") "Altium Limited"))
      (libsource (lib "*") (part "Res2"))
    )
    (comp (ref "R47")
      (value "1K-0805-5%")
      (footprint "0805")
      (description "Resistor")
      (fields (field (name "PUBLISHER") "Altium Limited"))
      (libsource (lib "*") (part "Res2"))
    )
    (comp (ref "R48")
      (value "5.1K-0805-5%")
      (footprint "0805")
      (description "Resistor")
      (fields (field (name "PUBLISHER") "Altium Limited"))
      (libsource (lib "*") (part "Res2"))
    )
    (comp (ref "R49")
      (value "5.1K-0805-5%")
      (footprint "0805")
      (description "Resistor")
      (fields (field (name "PUBLISHER") "Altium Limited"))
      (libsource (lib "Miscellaneous Devices") (part "Res2"))
    )
    (comp (ref "R50")
      (value "5.1K-0805-5%")
      (footprint "0805")
      (description "Resistor")
      (fields (field (name "PUBLISHER") "Altium Limited"))
      (libsource (lib "Miscellaneous Devices") (part "Res2"))
    )
    (comp (ref "R51")
      (value "5.1K-0805-5%")
      (footprint "0805")
      (description "Resistor")
      (fields (field (name "PUBLISHER") "Altium Limited"))
      (libsource (lib "Miscellaneous Devices") (part "Res2"))
    )
    (comp (ref "R52")
      (value "5.1K-0805-5%")
      (footprint "0805")
      (description "Resistor")
      (fields (field (name "PUBLISHER") "Altium Limited"))
      (libsource (lib "Miscellaneous Devices") (part "Res2"))
    )
    (comp (ref "R53")
      (value "5.1K-0805-5%")
      (footprint "0805")
      (description "Resistor")
      (fields (field (name "PUBLISHER") "Altium Limited"))
      (libsource (lib "Miscellaneous Devices") (part "Res2"))
    )
    (comp (ref "R54")
      (value "5.1K-0805-5%")
      (footprint "0805")
      (description "Resistor")
      (fields (field (name "PUBLISHER") "Altium Limited"))
      (libsource (lib "Miscellaneous Devices") (part "Res2"))
    )
    (comp (ref "R55")
      (value "5.1K-0805-5%")
      (footprint "0805")
      (description "Resistor")
      (fields (field (name "PUBLISHER") "Altium Limited"))
      (libsource (lib "Miscellaneous Devices") (part "Res2"))
    )
    (comp (ref "R56")
      (value "4.7K-0805-5%")
      (footprint "0805")
      (description "Resistor")
      (fields (field (name "PUBLISHER") "Altium Limited"))
      (libsource (lib "") (part "Res2_1"))
    )
    (comp (ref "R57")
      (value "4.7K-0805-5%")
      (footprint "0805")
      (description "Resistor")
      (fields (field (name "PUBLISHER") "Altium Limited"))
      (libsource (lib "") (part "Res2_1"))
    )
    (comp (ref "R58")
      (value "10K-0805-5%")
      (footprint "0805")
      (description "Resistor")
      (fields (field (name "PUBLISHER") "Altium Limited"))
      (libsource (lib "") (part "Res2_2"))
    )
    (comp (ref "R63")
      (value "120-0805-5%")
      (footprint "0805")
      (description "Resistor")
      (fields (field (name "PUBLISHER") "Altium Limited"))
      (libsource (lib "") (part "Res2_1"))
    )
    (comp (ref "R64")
      (value "100K-0805-5%")
      (footprint "0805")
      (description "Resistor")
      (fields (field (name "PUBLISHER") "Altium Limited"))
      (libsource (lib "Miscellaneous Devices") (part "Res2"))
    )
    (comp (ref "R65") (value "1K-0805-5%") (footprint "0805") (libsource (lib "*") (part "RES2")))
    (comp (ref "R66") (value "1K-0805-5%") (footprint "0805") (libsource (lib "*") (part "RES2")))
    (comp (ref "R67") (value "1K-0805-5%") (footprint "0805") (libsource (lib "*") (part "RES2")))
    (comp (ref "R68") (value "1K-0805-5%") (footprint "0805") (libsource (lib "*") (part "RES2")))
    (comp (ref "R69") (value "1K-0805-5%") (footprint "0805") (libsource (lib "*") (part "RES2")))
    (comp (ref "R70") (value "1K-0805-5%") (footprint "0805") (libsource (lib "*") (part "RES2")))
    (comp (ref "R71") (value "1K-0805-5%") (footprint "0805") (libsource (lib "*") (part "RES2")))
    (comp (ref "R72") (value "1K-0805-5%") (footprint "0805") (libsource (lib "*") (part "RES2")))
    (comp (ref "R73") (value "1K-0805-5%") (footprint "0805") (libsource (lib "*") (part "RES2")))
    (comp (ref "R74") (value "1K-0805-5%") (footprint "0805") (libsource (lib "*") (part "RES2")))
    (comp (ref "R75") (value "1K-0805-5%") (footprint "0805") (libsource (lib "*") (part "RES2")))
    (comp (ref "R76") (value "1K-0805-5%") (footprint "0805") (libsource (lib "*") (part "RES2")))
    (comp (ref "R77")
      (value "510-0805-5%")
      (footprint "0805")
      (description "Resistor")
      (fields (field (name "PUBLISHER") "Altium Limited"))
      (libsource (lib "Miscellaneous Devices") (part "Res2"))
    )
    (comp (ref "R78")
      (value "510-0805-5%")
      (footprint "0805")
      (description "Resistor")
      (fields (field (name "PUBLISHER") "Altium Limited"))
      (libsource (lib "Miscellaneous Devices") (part "Res2"))
    )
    (comp (ref "R79")
      (value "10K-0805-5%")
      (footprint "0805")
      (description "Resistor")
      (fields (field (name "PUBLISHER") "Altium Limited"))
      (libsource (lib "") (part "Res2_1"))
    )
    (comp (ref "R80")
      (value "10K-0805-5%")
      (footprint "0805")
      (description "Resistor")
      (fields (field (name "PUBLISHER") "Altium Limited"))
      (libsource (lib "") (part "Res2_1"))
    )
    (comp (ref "R81")
      (value "1K-0805-5%")
      (footprint "0805")
      (description "Resistor")
      (fields (field (name "PUBLISHER") "Altium Limited"))
      (libsource (lib "") (part "Res2_2"))
    )
    (comp (ref "R82")
      (value "1K-0805-5%")
      (footprint "0805")
      (description "Resistor")
      (fields (field (name "PUBLISHER") "Altium Limited"))
      (libsource (lib "") (part "Res2_2"))
    )
    (comp (ref "R83") (value "270-0805-5%") (footprint "0805") (libsource (lib "*") (part "RES2")))
    (comp (ref "R84") (value "270-0805-5%") (footprint "0805") (libsource (lib "*") (part "RES2")))
    (comp (ref "R85")
      (value "10K-0805-5%")
      (footprint "0805")
      (description "Resistor")
      (fields (field (name "PUBLISHER") "Altium Limited"))
      (libsource (lib "") (part "Res2_1"))
    )
    (comp (ref "R86")
      (value "10K-0805-5%")
      (footprint "0805")
      (description "Resistor")
      (fields (field (name "PUBLISHER") "Altium Limited"))
      (libsource (lib "") (part "Res2_1"))
    )
    (comp (ref "R87") (value "270-0805-5%") (footprint "0805") (libsource (lib "*") (part "RES2")))
    (comp (ref "R88") (value "270-0805-5%") (footprint "0805") (libsource (lib "*") (part "RES2")))
    (comp (ref "R89") (value "270-0805-5%") (footprint "0805") (libsource (lib "*") (part "RES2")))
    (comp (ref "R90") (value "270-0805-5%") (footprint "0805") (libsource (lib "*") (part "RES2")))
    (comp (ref "R91") (value "270-0805-5%") (footprint "0805") (libsource (lib "*") (part "RES2")))
    (comp (ref "R92")
      (value "510-0805-5%")
      (footprint "0805")
      (description "Resistor")
      (fields (field (name "PUBLISHER") "Altium Limited"))
      (libsource (lib "Miscellaneous Devices") (part "Res2"))
    )
    (comp (ref "R93")
      (value "510-0805-5%")
      (footprint "0805")
      (description "Resistor")
      (fields (field (name "PUBLISHER") "Altium Limited"))
      (libsource (lib "Miscellaneous Devices") (part "Res2"))
    )
    (comp (ref "R94") (value "10K-0805-5%") (footprint "0805") (libsource (lib "*") (part "RES2")))
    (comp (ref "R95")
      (value "10K-0805-5%")
      (footprint "0805")
      (description "Resistor")
      (fields (field (name "PUBLISHER") "Altium Limited"))
      (libsource (lib "") (part "Res2_1"))
    )
    (comp (ref "R96")
      (value "10K-0805-5%")
      (footprint "0805")
      (description "Resistor")
      (fields (field (name "PUBLISHER") "Altium Limited"))
      (libsource (lib "") (part "Res2_1"))
    )
    (comp (ref "R97")
      (value "1K-0805-5%")
      (footprint "0805")
      (description "Resistor")
      (fields (field (name "PUBLISHER") "Altium Limited"))
      (libsource (lib "") (part "Res2_2"))
    )
    (comp (ref "R98")
      (value "1K-0805-5%")
      (footprint "0805")
      (description "Resistor")
      (fields (field (name "PUBLISHER") "Altium Limited"))
      (libsource (lib "") (part "Res2_2"))
    )
    (comp (ref "R99") (value "10K-0805-5%") (footprint "0805") (libsource (lib "*") (part "RES2")))
    (comp (ref "R100") (value "10K-0805-5%") (footprint "0805") (libsource (lib "*") (part "RES2")))
    (comp (ref "R101") (value "10K-0805-5%") (footprint "0805") (libsource (lib "*") (part "RES2")))
    (comp (ref "R102")
      (value "10K-0805-5%")
      (footprint "0805")
      (description "Resistor")
      (fields (field (name "PUBLISHER") "Altium Limited"))
      (libsource (lib "") (part "Res2_1"))
    )
    (comp (ref "R103")
      (value "10K-0805-5%")
      (footprint "0805")
      (description "Resistor")
      (fields (field (name "PUBLISHER") "Altium Limited"))
      (libsource (lib "") (part "Res2_1"))
    )
    (comp (ref "R104") (value "10K-0805-5%") (footprint "0805") (libsource (lib "*") (part "RES2")))
    (comp (ref "R105") (value "10K-0805-5%") (footprint "0805") (libsource (lib "*") (part "RES2")))
    (comp (ref "R106") (value "0R-1206-5%") (footprint "1206") (libsource (lib "*") (part "RES2")))
    (comp (ref "R107") (value "1R5-1206-5%") (footprint "1206") (libsource (lib "*") (part "RES2")))
    (comp (ref "R108") (value "1R5-1206-5%") (footprint "1206") (libsource (lib "*") (part "RES2")))
    (comp (ref "R109")
      (value "510-0805-5%")
      (footprint "0805")
      (description "Resistor")
      (fields (field (name "PUBLISHER") "Altium Limited"))
      (libsource (lib "Miscellaneous Devices") (part "Res2"))
    )
    (comp (ref "R110")
      (value "10K-0805-5%")
      (footprint "0805")
      (description "Resistor")
      (fields (field (name "PUBLISHER") "Altium Limited"))
      (libsource (lib "") (part "Res2_1"))
    )
    (comp (ref "R111") (value "10K-0805-5%") (footprint "0805") (libsource (lib "*") (part "RES2")))
    (comp (ref "R112")
      (value "1K-0805-5%")
      (footprint "0805")
      (description "Resistor")
      (fields (field (name "PUBLISHER") "Altium Limited"))
      (libsource (lib "") (part "Res2_2"))
    )
    (comp (ref "R113") (value "10K-0805-5%") (footprint "0805") (libsource (lib "*") (part "RES2")))
    (comp (ref "R114")
      (value "10K-0805-5%")
      (footprint "0805")
      (description "Resistor")
      (fields (field (name "PUBLISHER") "Altium Limited"))
      (libsource (lib "") (part "Res2_1"))
    )
    (comp (ref "R115") (value "0R-1206-5%") (footprint "1206") (libsource (lib "*") (part "RES2")))
    (comp (ref "R116") (value "1K-0805-5%") (footprint "0805") (libsource (lib "") (part "RES2_1")))
    (comp (ref "R117") (value "1K-0805-5%") (footprint "0805") (libsource (lib "") (part "RES2_1")))
    (comp (ref "R118") (value "1K-0805-5%") (footprint "0805") (libsource (lib "*") (part "RES2")))
    (comp (ref "U1")
      (value "HXO-36B-8MHZ-7.0*5.0*1.5-SMD")
      (footprint "OSC_4_S")
      (libsource (lib "*") (part "CRYSTAL"))
    )
    (comp (ref "U2")
      (value "LM2576-5")
      (footprint "TO-263")
      (description "TO-263")
      (libsource (lib "SilvestStandardSchLib") (part "LM2576"))
    )
    (comp (ref "U3") (value "MAX3485") (footprint "PcbLib1:SOP8") (libsource (lib "*") (part "MAX3485")))
    (comp (ref "U5")
      (value "STM32F103VET6")
      (footprint "LQFP100_N")
      (libsource (lib "STM32") (part "STM32F103VET6"))
    )
    (comp (ref "U6")
      (value "LM1117MPX-3.3")
      (footprint "SOT-223-3L")
      (libsource (lib "PCB_Project1") (part "LM1117MPX-3.3"))
    )
    (comp (ref "U7") (value "'W25Q64BVSSIG") (footprint "SO-8M") (libsource (lib "*") (part "W25Q64")))
    (comp (ref "U8") (value "IRF7404PBF") (footprint "SO-8") (libsource (lib "*") (part "sop8(IRF7404)")))
    (comp (ref "U9")
      (value "ULN2003ADR")
      (footprint "SO-16")
      (description "Darlinton BJT Array")
      (libsource (lib "SilvestStandardSchLib") (part "ULN2003"))
    )
    (comp (ref "U11") (value "MAX3232ESE") (footprint "SOIC-16") (libsource (lib "*") (part "SPI3232E")))
    (comp (ref "U12") (value "MAX3232ESE") (footprint "SOIC-16") (libsource (lib "*") (part "SPI3232E")))
    (comp (ref "U14")
      (value "74HC14D")
      (footprint "SO-14")
      (description "Hex Inverters")
      (libsource (lib "SilvestStandardSchLib") (part "74HC04"))
    )
    (comp (ref "U15")
      (value "74HC14D")
      (footprint "SO-14")
      (description "Hex Inverters")
      (libsource (lib "SilvestStandardSchLib") (part "74HC04"))
    )
    (comp (ref "U16") (value "L298P") (footprint "POWERSO20_N") (libsource (lib "*") (part "L298P")))
    (comp (ref "U17")
      (value "LM393AD")
      (footprint "SO-8")
      (description "Low-Power Dual Voltage Comparator")
      (fields (field (name "PUBLISHER") "Altium Limited"))
      (libsource (lib "*") (part "LM393AD"))
    )
  )
  (nets
    (net (code "1") (name "+5V") (class "Default")
      (node (ref "C16") (pin "1") (pinfunction "1_1") (pintype "passive"))
      (node (ref "C19") (pin "1") (pinfunction "1_1") (pintype "passive"))
      (node (ref "C62") (pin "1") (pinfunction "1_1") (pintype "passive"))
      (node (ref "C63") (pin "1") (pinfunction "1_1") (pintype "passive"))
      (node (ref "C65") (pin "1") (pinfunction "1_1") (pintype "passive"))
      (node (ref "J4") (pin "10") (pinfunction "10_10") (pintype "passive"))
      (node (ref "J4") (pin "16") (pinfunction "16_16") (pintype "passive"))
      (node (ref "J4") (pin "4") (pinfunction "4_4") (pintype "passive"))
      (node (ref "J5") (pin "10") (pinfunction "10_10") (pintype "passive"))
      (node (ref "J5") (pin "16") (pinfunction "16_16") (pintype "passive"))
      (node (ref "J5") (pin "4") (pinfunction "4_4") (pintype "passive"))
      (node (ref "J6") (pin "10") (pinfunction "10_10") (pintype "passive"))
      (node (ref "J6") (pin "16") (pinfunction "16_16") (pintype "passive"))
      (node (ref "J6") (pin "4") (pinfunction "4_4") (pintype "passive"))
      (node (ref "J8") (pin "10") (pinfunction "10_10") (pintype "passive"))
      (node (ref "J8") (pin "16") (pinfunction "16_16") (pintype "passive"))
      (node (ref "J8") (pin "4") (pinfunction "4_4") (pintype "passive"))
      (node (ref "L1") (pin "2") (pinfunction "2_2") (pintype "passive"))
      (node (ref "R104") (pin "1") (pinfunction "1_1") (pintype "passive"))
      (node (ref "R105") (pin "1") (pinfunction "1_1") (pintype "passive"))
      (node (ref "R113") (pin "1") (pinfunction "1_1") (pintype "passive"))
      (node (ref "R12") (pin "1") (pinfunction "1_1") (pintype "passive"))
      (node (ref "R14") (pin "1") (pinfunction "1_1") (pintype "passive"))
      (node (ref "R26") (pin "1") (pinfunction "1_1") (pintype "passive"))
      (node (ref "R28") (pin "1") (pinfunction "1_1") (pintype "passive"))
      (node (ref "R30") (pin "1") (pinfunction "1_1") (pintype "passive"))
      (node (ref "R32") (pin "1") (pinfunction "1_1") (pintype "passive"))
      (node (ref "R34") (pin "1") (pinfunction "1_1") (pintype "passive"))
      (node (ref "R36") (pin "1") (pinfunction "1_1") (pintype "passive"))
      (node (ref "R38") (pin "1") (pinfunction "1_1") (pintype "passive"))
      (node (ref "R40") (pin "1") (pinfunction "1_1") (pintype "passive"))
      (node (ref "R42") (pin "1") (pinfunction "1_1") (pintype "passive"))
      (node (ref "R44") (pin "1") (pinfunction "1_1") (pintype "passive"))
      (node (ref "R46") (pin "1") (pinfunction "1_1") (pintype "passive"))
      (node (ref "R48") (pin "1") (pinfunction "1_1") (pintype "passive"))
      (node (ref "U14") (pin "14") (pinfunction "VCC_14") (pintype "passive"))
      (node (ref "U15") (pin "14") (pinfunction "VCC_14") (pintype "passive"))
      (node (ref "U16") (pin "12") (pinfunction "VCC_12") (pintype "passive"))
      (node (ref "U17") (pin "8") (pinfunction "V+_8") (pintype "power_in"))
      (node (ref "U2") (pin "4") (pinfunction "FB_4") (pintype "passive"))
      (node (ref "U6") (pin "3") (pinfunction "Vin_3") (pintype "passive"))
      (node (ref "U8") (pin "1") (pinfunction "S_1") (pintype "passive"))
      (node (ref "U8") (pin "2") (pinfunction "S_2") (pintype "passive"))
      (node (ref "U8") (pin "3") (pinfunction "S_3") (pintype "passive"))
    )
    (net (code "2") (name "/+24V") (class "Default")
      (node (ref "C17") (pin "1") (pinfunction "1_1") (pintype "passive"))
      (node (ref "C4") (pin "1") (pinfunction "1_1") (pintype "passive"))
      (node (ref "C8") (pin "1") (pinfunction "1_1") (pintype "passive"))
      (node (ref "D11") (pin "2") (pinfunction "K_2") (pintype "passive"))
      (node (ref "D13") (pin "2") (pinfunction "K_2") (pintype "passive"))
      (node (ref "J1") (pin "10") (pinfunction "10_10") (pintype "passive"))
      (node (ref "J1") (pin "12") (pinfunction "12_12") (pintype "passive"))
      (node (ref "J1") (pin "14") (pinfunction "14_14") (pintype "passive"))
      (node (ref "J1") (pin "16") (pinfunction "16_16") (pintype "passive"))
      (node (ref "J1") (pin "2") (pinfunction "2_2") (pintype "passive"))
      (node (ref "J1") (pin "4") (pinfunction "4_4") (pintype "passive"))
      (node (ref "J1") (pin "6") (pinfunction "6_6") (pintype "passive"))
      (node (ref "J1") (pin "8") (pinfunction "8_8") (pintype "passive"))
      (node (ref "R115") (pin "2") (pinfunction "2_2") (pintype "passive"))
      (node (ref "R16") (pin "1") (pinfunction "1_1") (pintype "passive"))
      (node (ref "R49") (pin "2") (pinfunction "2_2") (pintype "passive"))
      (node (ref "R50") (pin "2") (pinfunction "2_2") (pintype "passive"))
      (node (ref "R51") (pin "2") (pinfunction "2_2") (pintype "passive"))
      (node (ref "R52") (pin "2") (pinfunction "2_2") (pintype "passive"))
      (node (ref "R53") (pin "2") (pinfunction "2_2") (pintype "passive"))
      (node (ref "R54") (pin "2") (pinfunction "2_2") (pintype "passive"))
      (node (ref "R55") (pin "2") (pinfunction "2_2") (pintype "passive"))
      (node (ref "U2") (pin "1") (pinfunction "IN_1") (pintype "passive"))
    )
    (net (code "3") (name "/+24VA") (class "Default")
      (node (ref "C10") (pin "1") (pinfunction "1_1") (pintype "passive"))
      (node (ref "C13") (pin "1") (pinfunction "1_1") (pintype "passive"))
      (node (ref "C15") (pin "1") (pinfunction "1_1") (pintype "passive"))
      (node (ref "C67") (pin "1") (pinfunction "1_1") (pintype "passive"))
      (node (ref "D39") (pin "K") (pinfunction "K_K") (pintype "passive"))
      (node (ref "D40") (pin "K") (pinfunction "K_K") (pintype "passive"))
      (node (ref "D41") (pin "K") (pinfunction "K_K") (pintype "passive"))
      (node (ref "D42") (pin "K") (pinfunction "K_K") (pintype "passive"))
      (node (ref "D43") (pin "K") (pinfunction "K_K") (pintype "passive"))
      (node (ref "J14") (pin "1") (pinfunction "1_1") (pintype "passive"))
      (node (ref "J15") (pin "1") (pinfunction "1_1") (pintype "passive"))
      (node (ref "J16") (pin "1") (pinfunction "1_1") (pintype "passive"))
      (node (ref "J17") (pin "1") (pinfunction "1_1") (pintype "passive"))
      (node (ref "J19") (pin "1") (pinfunction "1_1") (pintype "passive"))
      (node (ref "Q10") (pin "2") (pintype "passive"))
      (node (ref "Q7") (pin "2") (pintype "passive"))
      (node (ref "Q8") (pin "2") (pintype "passive"))
      (node (ref "Q9") (pin "2") (pintype "passive"))
      (node (ref "R102") (pin "1") (pinfunction "1_1") (pintype "passive"))
      (node (ref "R103") (pin "1") (pinfunction "1_1") (pintype "passive"))
      (node (ref "R114") (pin "1") (pinfunction "1_1") (pintype "passive"))
      (node (ref "R115") (pin "1") (pinfunction "1_1") (pintype "passive"))
      (node (ref "R85") (pin "1") (pinfunction "1_1") (pintype "passive"))
      (node (ref "R86") (pin "1") (pinfunction "1_1") (pintype "passive"))
      (node (ref "U16") (pin "6") (pinfunction "Vhi_6") (pintype "passive"))
    )
    (net (code "4") (name "/+24VIN") (class "Default")
      (node (ref "F1") (pin "1") (pinfunction "1_1") (pintype "passive"))
      (node (ref "J2") (pin "1") (pinfunction "1_1") (pintype "passive"))
      (node (ref "J2") (pin "3") (pinfunction "3_3") (pintype "passive"))
      (node (ref "J3") (pin "1") (pinfunction "1_1") (pintype "passive"))
      (node (ref "J3") (pin "3") (pinfunction "3_3") (pintype "passive"))
    )
    (net (code "5") (name "/5V_LED") (class "Default")
      (node (ref "R25") (pin "1") (pinfunction "1_1") (pintype "passive"))
      (node (ref "R27") (pin "1") (pinfunction "1_1") (pintype "passive"))
      (node (ref "R29") (pin "1") (pinfunction "1_1") (pintype "passive"))
      (node (ref "R31") (pin "1") (pinfunction "1_1") (pintype "passive"))
      (node (ref "R33") (pin "1") (pinfunction "1_1") (pintype "passive"))
      (node (ref "R35") (pin "1") (pinfunction "1_1") (pintype "passive"))
      (node (ref "R37") (pin "1") (pinfunction "1_1") (pintype "passive"))
      (node (ref "R39") (pin "1") (pinfunction "1_1") (pintype "passive"))
      (node (ref "R41") (pin "1") (pinfunction "1_1") (pintype "passive"))
      (node (ref "R43") (pin "1") (pinfunction "1_1") (pintype "passive"))
      (node (ref "R45") (pin "1") (pinfunction "1_1") (pintype "passive"))
      (node (ref "R47") (pin "1") (pinfunction "1_1") (pintype "passive"))
      (node (ref "U8") (pin "5") (pinfunction "D_5") (pintype "passive"))
      (node (ref "U8") (pin "6") (pinfunction "D_6") (pintype "passive"))
      (node (ref "U8") (pin "7") (pinfunction "D_7") (pintype "passive"))
      (node (ref "U8") (pin "8") (pinfunction "D_8") (pintype "passive"))
    )
    (net (code "6") (name "/485_A") (class "Default")
      (node (ref "J13") (pin "2") (pinfunction "2_2") (pintype "passive"))
      (node (ref "R57") (pin "1") (pinfunction "1_1") (pintype "passive"))
      (node (ref "R63") (pin "2") (pinfunction "2_2") (pintype "passive"))
      (node (ref "U3") (pin "6") (pinfunction "A_6") (pintype "passive"))
    )
    (net (code "7") (name "/485_B") (class "Default")
      (node (ref "J13") (pin "1") (pinfunction "1_1") (pintype "passive"))
      (node (ref "R56") (pin "2") (pinfunction "2_2") (pintype "passive"))
      (node (ref "R63") (pin "1") (pinfunction "1_1") (pintype "passive"))
      (node (ref "U3") (pin "7") (pinfunction "B_7") (pintype "passive"))
    )
    (net (code "8") (name "/485_EN") (class "Default")
      (node (ref "R58") (pin "2") (pinfunction "2_2") (pintype "passive"))
      (node (ref "U3") (pin "2") (pinfunction "/RE_2") (pintype "passive"))
      (node (ref "U3") (pin "3") (pinfunction "DE_3") (pintype "passive"))
      (node (ref "U5") (pin "84") (pinfunction "PD3_84") (pintype "passive"))
    )
    (net (code "9") (name "/BOOT0") (class "Default")
      (node (ref "R64") (pin "2") (pinfunction "2_2") (pintype "passive"))
      (node (ref "U5") (pin "94") (pinfunction "BOOT0_94") (pintype "passive"))
    )
    (net (code "10") (name "/BOOT1") (class "Default")
      (node (ref "R24") (pin "2") (pinfunction "2_2") (pintype "passive"))
      (node (ref "U5") (pin "37") (pinfunction "PB2_37") (pintype "passive"))
    )
    (net (code "11") (name "/CLK_IN") (class "Default")
      (node (ref "U1") (pin "3") (pinfunction "CLK_3") (pintype "passive"))
      (node (ref "U5") (pin "12") (pinfunction "OSC_IN_12") (pintype "passive"))
    )
    (net (code "12") (name "/FLASH_CS") (class "Default")
      (node (ref "U5") (pin "29") (pinfunction "PA4_29") (pintype "passive"))
      (node (ref "U7") (pin "1") (pinfunction "CS_1") (pintype "passive"))
    )
    (net (code "13") (name "/G1") (class "Default")
      (node (ref "J11") (pin "8") (pinfunction "8_8") (pintype "passive"))
      (node (ref "U5") (pin "33") (pinfunction "PC4_33") (pintype "passive"))
    )
    (net (code "14") (name "/G2") (class "Default")
      (node (ref "J11") (pin "10") (pinfunction "10_10") (pintype "passive"))
      (node (ref "U5") (pin "34") (pinfunction "PC5_34") (pintype "passive"))
    )
    (net (code "15") (name "/G3") (class "Default")
      (node (ref "J11") (pin "9") (pinfunction "9_9") (pintype "passive"))
      (node (ref "U5") (pin "35") (pinfunction "PB0_35") (pintype "passive"))
    )
    (net (code "16") (name "/G4") (class "Default")
      (node (ref "J11") (pin "11") (pinfunction "11_11") (pintype "passive"))
      (node (ref "U5") (pin "82") (pinfunction "PD1_82") (pintype "passive"))
    )
    (net (code "17") (name "/G5") (class "Default")
      (node (ref "J11") (pin "12") (pinfunction "12_12") (pintype "passive"))
      (node (ref "U5") (pin "81") (pinfunction "PD0_81") (pintype "passive"))
    )
    (net (code "18") (name "/IN1") (class "Default")
      (node (ref "C21") (pin "2") (pinfunction "2_2") (pintype "passive"))
      (node (ref "D2") (pin "2") (pinfunction "K_2") (pintype "passive"))
      (node (ref "D44") (pin "A") (pinfunction "A_A") (pintype "passive"))
      (node (ref "R1") (pin "2") (pinfunction "2_2") (pintype "passive"))
      (node (ref "U5") (pin "85") (pinfunction "PD4_85") (pintype "passive"))
    )
    (net (code "19") (name "/IN2") (class "Default")
      (node (ref "C22") (pin "2") (pinfunction "2_2") (pintype "passive"))
      (node (ref "D3") (pin "2") (pinfunction "K_2") (pintype "passive"))
      (node (ref "D45") (pin "A") (pinfunction "A_A") (pintype "passive"))
      (node (ref "R2") (pin "2") (pinfunction "2_2") (pintype "passive"))
      (node (ref "U5") (pin "86") (pinfunction "PD5_86") (pintype "passive"))
    )
    (net (code "20") (name "/IN3") (class "Default")
      (node (ref "C23") (pin "2") (pinfunction "2_2") (pintype "passive"))
      (node (ref "D4") (pin "2") (pinfunction "K_2") (pintype "passive"))
      (node (ref "D46") (pin "A") (pinfunction "A_A") (pintype "passive"))
      (node (ref "R3") (pin "2") (pinfunction "2_2") (pintype "passive"))
      (node (ref "U5") (pin "87") (pinfunction "PD6_87") (pintype "passive"))
    )
    (net (code "21") (name "/IN4") (class "Default")
      (node (ref "C24") (pin "2") (pinfunction "2_2") (pintype "passive"))
      (node (ref "D47") (pin "A") (pinfunction "A_A") (pintype "passive"))
      (node (ref "D5") (pin "2") (pinfunction "K_2") (pintype "passive"))
      (node (ref "R4") (pin "2") (pinfunction "2_2") (pintype "passive"))
      (node (ref "U5") (pin "88") (pinfunction "PD7_88") (pintype "passive"))
    )
    (net (code "22") (name "/IN5") (class "Default")
      (node (ref "C25") (pin "2") (pinfunction "2_2") (pintype "passive"))
      (node (ref "D48") (pin "A") (pinfunction "A_A") (pintype "passive"))
      (node (ref "D6") (pin "2") (pinfunction "K_2") (pintype "passive"))
      (node (ref "R5") (pin "2") (pinfunction "2_2") (pintype "passive"))
      (node (ref "U5") (pin "91") (pinfunction "PB5_91") (pintype "passive"))
    )
    (net (code "23") (name "/IN6") (class "Default")
      (node (ref "C27") (pin "2") (pinfunction "2_2") (pintype "passive"))
      (node (ref "D49") (pin "A") (pinfunction "A_A") (pintype "passive"))
      (node (ref "D7") (pin "2") (pinfunction "K_2") (pintype "passive"))
      (node (ref "R6") (pin "2") (pinfunction "2_2") (pintype "passive"))
      (node (ref "U5") (pin "92") (pinfunction "PB6_92") (pintype "passive"))
    )
    (net (code "24") (name "/MOTOR1+") (class "Default")
      (node (ref "J18") (pin "4") (pinfunction "4_4") (pintype "passive"))
      (node (ref "Q10") (pin "3") (pintype "passive"))
      (node (ref "U16") (pin "4") (pinfunction "OUT1_4") (pintype "passive"))
    )
    (net (code "25") (name "/MOTOR1-") (class "Default")
      (node (ref "J18") (pin "3") (pinfunction "3_3") (pintype "passive"))
      (node (ref "Q7") (pin "3") (pintype "passive"))
      (node (ref "U16") (pin "5") (pinfunction "OUT2_5") (pintype "passive"))
    )
    (net (code "26") (name "/MOTOR2+") (class "Default")
      (node (ref "J18") (pin "2") (pinfunction "2_2") (pintype "passive"))
      (node (ref "Q8") (pin "3") (pintype "passive"))
      (node (ref "U16") (pin "16") (pinfunction "OUT3_16") (pintype "passive"))
    )
    (net (code "27") (name "/MOTOR2-") (class "Default")
      (node (ref "J18") (pin "1") (pinfunction "1_1") (pintype "passive"))
      (node (ref "Q9") (pin "3") (pintype "passive"))
      (node (ref "U16") (pin "17") (pinfunction "OUT4_17") (pintype "passive"))
    )
    (net (code "28") (name "/MOTOR_1F+") (class "Default")
      (node (ref "R94") (pin "2") (pinfunction "2_2") (pintype "passive"))
      (node (ref "U16") (pin "7") (pinfunction "IN1_7") (pintype "passive"))
      (node (ref "U5") (pin "3") (pinfunction "PE4_3") (pintype "passive"))
    )
    (net (code "29") (name "/MOTOR_1F-") (class "Default")
      (node (ref "R99") (pin "2") (pinfunction "2_2") (pintype "passive"))
      (node (ref "U16") (pin "9") (pinfunction "IN2_9") (pintype "passive"))
      (node (ref "U5") (pin "4") (pinfunction "PE5_4") (pintype "passive"))
    )
    (net (code "30") (name "/MOTOR_2F+") (class "Default")
      (node (ref "R100") (pin "2") (pinfunction "2_2") (pintype "passive"))
      (node (ref "U16") (pin "13") (pinfunction "IN3_13") (pintype "passive"))
      (node (ref "U5") (pin "7") (pinfunction "PC13-TAMPER-RTC_7") (pintype "passive"))
    )
    (net (code "31") (name "/MOTOR_2F-") (class "Default")
      (node (ref "R101") (pin "2") (pinfunction "2_2") (pintype "passive"))
      (node (ref "U16") (pin "15") (pinfunction "IN4_15") (pintype "passive"))
      (node (ref "U5") (pin "5") (pinfunction "PE6_5") (pintype "passive"))
    )
    (net (code "32") (name "/NSRST") (class "Default")
      (node (ref "C2") (pin "2") (pinfunction "2_2") (pintype "passive"))
      (node (ref "J7") (pin "15") (pinfunction "NSRST_15") (pintype "passive"))
      (node (ref "K3") (pin "2") (pinfunction "2_2") (pintype "passive"))
      (node (ref "R13") (pin "1") (pinfunction "1_1") (pintype "passive"))
      (node (ref "U5") (pin "14") (pinfunction "NRST_14") (pintype "passive"))
    )
    (net (code "33") (name "/NTRST") (class "Default")
      (node (ref "J7") (pin "3") (pinfunction "NTRST_3") (pintype "passive"))
      (node (ref "U5") (pin "90") (pinfunction "PB4_90") (pintype "passive"))
    )
    (net (code "34") (name "/OUT1") (class "Default")
      (node (ref "U5") (pin "44") (pinfunction "PE13_44") (pintype "passive"))
      (node (ref "U9") (pin "1") (pinfunction "IN1_1") (pintype "passive"))
    )
    (net (code "35") (name "/OUT2") (class "Default")
      (node (ref "U5") (pin "43") (pinfunction "PE12_43") (pintype "passive"))
      (node (ref "U9") (pin "2") (pinfunction "IN2_2") (pintype "passive"))
    )
    (net (code "36") (name "/OUT3") (class "Default")
      (node (ref "U5") (pin "42") (pinfunction "PE11_42") (pintype "passive"))
      (node (ref "U9") (pin "3") (pinfunction "IN3_3") (pintype "passive"))
    )
    (net (code "37") (name "/OUT4") (class "Default")
      (node (ref "U5") (pin "41") (pinfunction "PE10_41") (pintype "passive"))
      (node (ref "U9") (pin "4") (pinfunction "IN4_4") (pintype "passive"))
    )
    (net (code "38") (name "/OUT5") (class "Default")
      (node (ref "U5") (pin "40") (pinfunction "PE9_40") (pintype "passive"))
      (node (ref "U9") (pin "5") (pinfunction "IN5_5") (pintype "passive"))
    )
    (net (code "39") (name "/OUT6") (class "Default")
      (node (ref "U5") (pin "39") (pinfunction "PE8_39") (pintype "passive"))
      (node (ref "U9") (pin "6") (pinfunction "IN6_6") (pintype "passive"))
    )
    (net (code "40") (name "/OUT7") (class "Default")
      (node (ref "U5") (pin "38") (pinfunction "PE7_38") (pintype "passive"))
      (node (ref "U9") (pin "7") (pinfunction "IN7_7") (pintype "passive"))
    )
    (net (code "41") (name "/OUT_1") (class "Default")
      (node (ref "D14") (pin "2") (pinfunction "K_2") (pintype "passive"))
      (node (ref "J1") (pin "1") (pinfunction "1_1") (pintype "passive"))
      (node (ref "U9") (pin "16") (pinfunction "OUT1_16") (pintype "passive"))
    )
    (net (code "42") (name "/OUT_2") (class "Default")
      (node (ref "D16") (pin "2") (pinfunction "K_2") (pintype "passive"))
      (node (ref "J1") (pin "3") (pinfunction "3_3") (pintype "passive"))
      (node (ref "U9") (pin "15") (pinfunction "OUT2_15") (pintype "passive"))
    )
    (net (code "43") (name "/OUT_3") (class "Default")
      (node (ref "D17") (pin "2") (pinfunction "K_2") (pintype "passive"))
      (node (ref "J1") (pin "5") (pinfunction "5_5") (pintype "passive"))
      (node (ref "U9") (pin "14") (pinfunction "OUT3_14") (pintype "passive"))
    )
    (net (code "44") (name "/OUT_4") (class "Default")
      (node (ref "D18") (pin "2") (pinfunction "K_2") (pintype "passive"))
      (node (ref "J1") (pin "7") (pinfunction "7_7") (pintype "passive"))
      (node (ref "U9") (pin "13") (pinfunction "OUT4_13") (pintype "passive"))
    )
    (net (code "45") (name "/OUT_5") (class "Default")
      (node (ref "D19") (pin "2") (pinfunction "K_2") (pintype "passive"))
      (node (ref "J1") (pin "9") (pinfunction "9_9") (pintype "passive"))
      (node (ref "U9") (pin "12") (pinfunction "OUT5_12") (pintype "passive"))
    )
    (net (code "46") (name "/OUT_6") (class "Default")
      (node (ref "D20") (pin "2") (pinfunction "K_2") (pintype "passive"))
      (node (ref "J1") (pin "11") (pinfunction "11_11") (pintype "passive"))
      (node (ref "U9") (pin "11") (pinfunction "OUT6_11") (pintype "passive"))
    )
    (net (code "47") (name "/OUT_7") (class "Default")
      (node (ref "D21") (pin "2") (pinfunction "K_2") (pintype "passive"))
      (node (ref "J1") (pin "13") (pinfunction "13_13") (pintype "passive"))
      (node (ref "U9") (pin "10") (pinfunction "OUT7_10") (pintype "passive"))
    )
    (net (code "48") (name "/RST") (class "Default")
      (node (ref "J11") (pin "7") (pinfunction "7_7") (pintype "passive"))
      (node (ref "U5") (pin "36") (pinfunction "PB1_36") (pintype "passive"))
    )
    (net (code "49") (name "/RXD1") (class "Default")
      (node (ref "U12") (pin "9") (pinfunction "R2OUT_9") (pintype "passive"))
      (node (ref "U3") (pin "1") (pinfunction "RO_1") (pintype "passive"))
      (node (ref "U5") (pin "69") (pinfunction "PA10_69") (pintype "passive"))
    )
    (net (code "50") (name "/RXD2") (class "Default")
      (node (ref "U11") (pin "12") (pinfunction "R1OUT_12") (pintype "passive"))
      (node (ref "U5") (pin "26") (pinfunction "PA3_26") (pintype "passive"))
    )
    (net (code "51") (name "/RXD3") (class "Default")
      (node (ref "U11") (pin "9") (pinfunction "R2OUT_9") (pintype "passive"))
      (node (ref "U5") (pin "48") (pinfunction "PB11_48") (pintype "passive"))
    )
    (net (code "52") (name "/RXD4") (class "Default")
      (node (ref "U5") (pin "79") (pinfunction "PC11_79") (pintype "passive"))
    )
    (net (code "53") (name "/RXD5") (class "Default")
      (node (ref "U5") (pin "83") (pinfunction "PD2_83") (pintype "passive+no_connect"))
    )
    (net (code "54") (name "/RXD_M1") (class "Default")
      (node (ref "J10") (pin "1") (pinfunction "1_1") (pintype "passive"))
      (node (ref "U12") (pin "7") (pinfunction "T2OUT_7") (pintype "passive"))
    )
    (net (code "55") (name "/RXD_M2") (class "Default")
      (node (ref "J9") (pin "1") (pinfunction "1_1") (pintype "passive"))
      (node (ref "U11") (pin "14") (pinfunction "T1OUT_14") (pintype "passive"))
    )
    (net (code "56") (name "/RXD_M3") (class "Default")
      (node (ref "J9") (pin "4") (pinfunction "4_4") (pintype "passive"))
      (node (ref "U11") (pin "7") (pinfunction "T2OUT_7") (pintype "passive"))
    )
    (net (code "57") (name "/SENS1") (class "Default")
      (node (ref "R65") (pin "1") (pinfunction "1_1") (pintype "passive"))
      (node (ref "U14") (pin "12") (pinfunction "6Y_12") (pintype "passive"))
      (node (ref "U5") (pin "67") (pinfunction "PA8_67") (pintype "passive"))
    )
    (net (code "58") (name "/SENS2") (class "Default")
      (node (ref "R66") (pin "1") (pinfunction "1_1") (pintype "passive"))
      (node (ref "U14") (pin "10") (pinfunction "5Y_10") (pintype "passive"))
      (node (ref "U5") (pin "66") (pinfunction "PC9_66") (pintype "passive"))
    )
    (net (code "59") (name "/SENS3") (class "Default")
      (node (ref "R67") (pin "1") (pinfunction "1_1") (pintype "passive"))
      (node (ref "U14") (pin "8") (pinfunction "4Y_8") (pintype "passive"))
      (node (ref "U5") (pin "65") (pinfunction "PC8_65") (pintype "passive"))
    )
    (net (code "60") (name "/SENS4") (class "Default")
      (node (ref "R68") (pin "1") (pinfunction "1_1") (pintype "passive"))
      (node (ref "U14") (pin "6") (pinfunction "3Y_6") (pintype "passive"))
      (node (ref "U5") (pin "64") (pinfunction "PC7_64") (pintype "passive"))
    )
    (net (code "61") (name "/SENS5") (class "Default")
      (node (ref "R69") (pin "1") (pinfunction "1_1") (pintype "passive"))
      (node (ref "U14") (pin "4") (pinfunction "2Y_4") (pintype "passive"))
      (node (ref "U5") (pin "63") (pinfunction "PC6_63") (pintype "passive"))
    )
    (net (code "62") (name "/SENS6") (class "Default")
      (node (ref "R70") (pin "1") (pinfunction "1_1") (pintype "passive"))
      (node (ref "U14") (pin "2") (pinfunction "1Y_2") (pintype "passive"))
      (node (ref "U5") (pin "62") (pinfunction "PD15_62") (pintype "passive"))
    )
    (net (code "63") (name "/SENS7") (class "Default")
      (node (ref "R71") (pin "1") (pinfunction "1_1") (pintype "passive"))
      (node (ref "U15") (pin "12") (pinfunction "6Y_12") (pintype "passive"))
      (node (ref "U5") (pin "61") (pinfunction "PD14_61") (pintype "passive"))
    )
    (net (code "64") (name "/SENS8") (class "Default")
      (node (ref "R72") (pin "1") (pinfunction "1_1") (pintype "passive"))
      (node (ref "U15") (pin "10") (pinfunction "5Y_10") (pintype "passive"))
      (node (ref "U5") (pin "60") (pinfunction "PD13_60") (pintype "passive"))
    )
    (net (code "65") (name "/SENS9") (class "Default")
      (node (ref "R73") (pin "1") (pinfunction "1_1") (pintype "passive"))
      (node (ref "U15") (pin "8") (pinfunction "4Y_8") (pintype "passive"))
      (node (ref "U5") (pin "59") (pinfunction "PD12_59") (pintype "passive"))
    )
    (net (code "66") (name "/SENS10") (class "Default")
      (node (ref "R74") (pin "1") (pinfunction "1_1") (pintype "passive"))
      (node (ref "U15") (pin "6") (pinfunction "3Y_6") (pintype "passive"))
      (node (ref "U5") (pin "58") (pinfunction "PD11_58") (pintype "passive"))
    )
    (net (code "67") (name "/SENS11") (class "Default")
      (node (ref "R75") (pin "1") (pinfunction "1_1") (pintype "passive"))
      (node (ref "U15") (pin "4") (pinfunction "2Y_4") (pintype "passive"))
      (node (ref "U5") (pin "57") (pinfunction "PD10_57") (pintype "passive"))
    )
    (net (code "68") (name "/SENS12") (class "Default")
      (node (ref "R76") (pin "1") (pinfunction "1_1") (pintype "passive"))
      (node (ref "U15") (pin "2") (pinfunction "1Y_2") (pintype "passive"))
      (node (ref "U5") (pin "56") (pinfunction "PD9_56") (pintype "passive"))
    )
    (net (code "69") (name "/SENSER1") (class "Default")
      (node (ref "C42") (pin "1") (pinfunction "1_1") (pintype "passive"))
      (node (ref "J4") (pin "18") (pinfunction "18_18") (pintype "passive"))
      (node (ref "R42") (pin "2") (pinfunction "2_2") (pintype "passive"))
      (node (ref "U14") (pin "13") (pinfunction "6A_13") (pintype "passive"))
    )
    (net (code "70") (name "/SENSER2") (class "Default")
      (node (ref "C46") (pin "1") (pinfunction "1_1") (pintype "passive"))
      (node (ref "J4") (pin "12") (pinfunction "12_12") (pintype "passive"))
      (node (ref "R40") (pin "2") (pinfunction "2_2") (pintype "passive"))
      (node (ref "U14") (pin "11") (pinfunction "5A_11") (pintype "passive"))
    )
    (net (code "71") (name "/SENSER3") (class "Default")
      (node (ref "C38") (pin "1") (pinfunction "1_1") (pintype "passive"))
      (node (ref "J4") (pin "6") (pinfunction "6_6") (pintype "passive"))
      (node (ref "R38") (pin "2") (pinfunction "2_2") (pintype "passive"))
      (node (ref "U14") (pin "9") (pinfunction "4A_9") (pintype "passive"))
    )
    (net (code "72") (name "/SENSER4") (class "Default")
      (node (ref "C43") (pin "1") (pinfunction "1_1") (pintype "passive"))
      (node (ref "J5") (pin "18") (pinfunction "18_18") (pintype "passive"))
      (node (ref "R36") (pin "2") (pinfunction "2_2") (pintype "passive"))
      (node (ref "U14") (pin "5") (pinfunction "3A_5") (pintype "passive"))
    )
    (net (code "73") (name "/SENSER5") (class "Default")
      (node (ref "C47") (pin "1") (pinfunction "1_1") (pintype "passive"))
      (node (ref "J5") (pin "12") (pinfunction "12_12") (pintype "passive"))
      (node (ref "R34") (pin "2") (pinfunction "2_2") (pintype "passive"))
      (node (ref "U14") (pin "3") (pinfunction "2A_3") (pintype "passive"))
    )
    (net (code "74") (name "/SENSER6") (class "Default")
      (node (ref "C39") (pin "1") (pinfunction "1_1") (pintype "passive"))
      (node (ref "J5") (pin "6") (pinfunction "6_6") (pintype "passive"))
      (node (ref "R32") (pin "2") (pinfunction "2_2") (pintype "passive"))
      (node (ref "U14") (pin "1") (pinfunction "1A_1") (pintype "passive"))
    )
    (net (code "75") (name "/SENSER7") (class "Default")
      (node (ref "C44") (pin "1") (pinfunction "1_1") (pintype "passive"))
      (node (ref "J6") (pin "18") (pinfunction "18_18") (pintype "passive"))
      (node (ref "R30") (pin "2") (pinfunction "2_2") (pintype "passive"))
      (node (ref "U15") (pin "13") (pinfunction "6A_13") (pintype "passive"))
    )
    (net (code "76") (name "/SENSER8") (class "Default")
      (node (ref "C48") (pin "1") (pinfunction "1_1") (pintype "passive"))
      (node (ref "J6") (pin "12") (pinfunction "12_12") (pintype "passive"))
      (node (ref "R28") (pin "2") (pinfunction "2_2") (pintype "passive"))
      (node (ref "U15") (pin "11") (pinfunction "5A_11") (pintype "passive"))
    )
    (net (code "77") (name "/SENSER9") (class "Default")
      (node (ref "C40") (pin "1") (pinfunction "1_1") (pintype "passive"))
      (node (ref "J6") (pin "6") (pinfunction "6_6") (pintype "passive"))
      (node (ref "R26") (pin "2") (pinfunction "2_2") (pintype "passive"))
      (node (ref "U15") (pin "9") (pinfunction "4A_9") (pintype "passive"))
    )
    (net (code "78") (name "/SENSER10") (class "Default")
      (node (ref "C45") (pin "1") (pinfunction "1_1") (pintype "passive"))
      (node (ref "J8") (pin "18") (pinfunction "18_18") (pintype "passive"))
      (node (ref "R48") (pin "2") (pinfunction "2_2") (pintype "passive"))
      (node (ref "U15") (pin "5") (pinfunction "3A_5") (pintype "passive"))
    )
    (net (code "79") (name "/SENSER11") (class "Default")
      (node (ref "C49") (pin "1") (pinfunction "1_1") (pintype "passive"))
      (node (ref "J8") (pin "12") (pinfunction "12_12") (pintype "passive"))
      (node (ref "R46") (pin "2") (pinfunction "2_2") (pintype "passive"))
      (node (ref "U15") (pin "3") (pinfunction "2A_3") (pintype "passive"))
    )
    (net (code "80") (name "/SENSER12") (class "Default")
      (node (ref "C41") (pin "1") (pinfunction "1_1") (pintype "passive"))
      (node (ref "J8") (pin "6") (pinfunction "6_6") (pintype "passive"))
      (node (ref "R44") (pin "2") (pinfunction "2_2") (pintype "passive"))
      (node (ref "U15") (pin "1") (pinfunction "1A_1") (pintype "passive"))
    )
    (net (code "81") (name "/SENS_POWER") (class "Default")
      (node (ref "P1") (pin "1") (pinfunction "A_1") (pintype "passive"))
      (node (ref "U5") (pin "55") (pinfunction "PD8_55") (pintype "passive"))
    )
    (net (code "82") (name "/SOLE-1") (class "Default")
      (node (ref "P4") (pin "1") (pinfunction "A_1") (pintype "passive"))
      (node (ref "U5") (pin "98") (pinfunction "PE1_98") (pintype "passive"))
    )
    (net (code "83") (name "/SOLE-2") (class "Default")
      (node (ref "P5") (pin "1") (pinfunction "A_1") (pintype "passive"))
      (node (ref "U5") (pin "97") (pinfunction "PE0_97") (pintype "passive"))
    )
    (net (code "84") (name "/SOLE-3") (class "Default")
      (node (ref "P6") (pin "1") (pinfunction "A_1") (pintype "passive"))
      (node (ref "U5") (pin "96") (pinfunction "PB9_96") (pintype "passive"))
    )
    (net (code "85") (name "/SOLE-4") (class "Default")
      (node (ref "P7") (pin "1") (pinfunction "A_1") (pintype "passive"))
      (node (ref "U5") (pin "95") (pinfunction "PB8_95") (pintype "passive"))
    )
    (net (code "86") (name "/SOLE-5") (class "Default")
      (node (ref "P8") (pin "1") (pinfunction "A_1") (pintype "passive"))
      (node (ref "U5") (pin "93") (pinfunction "PB7_93") (pintype "passive"))
    )
    (net (code "87") (name "/SP") (class "Default")
      (node (ref "P1") (pin "4") (pinfunction "C_4") (pintype "passive"))
      (node (ref "R12") (pin "2") (pinfunction "2_2") (pintype "passive"))
      (node (ref "U8") (pin "4") (pinfunction "G_4") (pintype "passive"))
    )
    (net (code "88") (name "/SPI1_MISO") (class "Default")
      (node (ref "U5") (pin "31") (pinfunction "PA6_31") (pintype "passive"))
      (node (ref "U7") (pin "2") (pinfunction "SO_2") (pintype "passive"))
    )
    (net (code "89") (name "/SPI1_MOSI") (class "Default")
      (node (ref "U5") (pin "32") (pinfunction "PA7_32") (pintype "passive"))
      (node (ref "U7") (pin "5") (pinfunction "SI_5") (pintype "passive"))
    )
    (net (code "90") (name "/SPI1_SCK") (class "Default")
      (node (ref "U5") (pin "30") (pinfunction "PA5_30") (pintype "passive"))
      (node (ref "U7") (pin "6") (pinfunction "CLK_6") (pintype "passive"))
    )
    (net (code "91") (name "/SPI2_MISO") (class "Default")
      (node (ref "J11") (pin "5") (pinfunction "5_5") (pintype "passive"))
      (node (ref "U5") (pin "53") (pinfunction "PB14_53") (pintype "passive"))
    )
    (net (code "92") (name "/SPI2_MOSI") (class "Default")
      (node (ref "J11") (pin "6") (pinfunction "6_6") (pintype "passive"))
      (node (ref "U5") (pin "54") (pinfunction "PB15_54") (pintype "passive"))
    )
    (net (code "93") (name "/SPI2_NSS") (class "Default")
      (node (ref "J11") (pin "4") (pinfunction "4_4") (pintype "passive"))
      (node (ref "U5") (pin "51") (pinfunction "PB12_51") (pintype "passive"))
    )
    (net (code "94") (name "/SPI2_SCK") (class "Default")
      (node (ref "J11") (pin "3") (pinfunction "3_3") (pintype "passive"))
      (node (ref "U5") (pin "52") (pinfunction "PB13_52") (pintype "passive"))
    )
    (net (code "95") (name "/Switch1") (class "Default")
      (node (ref "D44") (pin "K") (pinfunction "K_K") (pintype "passive"))
      (node (ref "J20") (pin "11") (pinfunction "11_11") (pintype "passive"))
    )
    (net (code "96") (name "/Switch2") (class "Default")
      (node (ref "D45") (pin "K") (pinfunction "K_K") (pintype "passive"))
      (node (ref "J20") (pin "9") (pinfunction "9_9") (pintype "passive"))
    )
    (net (code "97") (name "/Switch3") (class "Default")
      (node (ref "D46") (pin "K") (pinfunction "K_K") (pintype "passive"))
      (node (ref "J20") (pin "7") (pinfunction "7_7") (pintype "passive"))
    )
    (net (code "98") (name "/Switch4") (class "Default")
      (node (ref "D47") (pin "K") (pinfunction "K_K") (pintype "passive"))
      (node (ref "J20") (pin "5") (pinfunction "5_5") (pintype "passive"))
    )
    (net (code "99") (name "/Switch5") (class "Default")
      (node (ref "D48") (pin "K") (pinfunction "K_K") (pintype "passive"))
      (node (ref "J20") (pin "3") (pinfunction "3_3") (pintype "passive"))
    )
    (net (code "100") (name "/Switch6") (class "Default")
      (node (ref "D49") (pin "K") (pinfunction "K_K") (pintype "passive"))
      (node (ref "J20") (pin "1") (pinfunction "1_1") (pintype "passive"))
    )
    (net (code "101") (name "/TCK") (class "Default")
      (node (ref "J7") (pin "9") (pinfunction "TCK_9") (pintype "passive"))
      (node (ref "U5") (pin "76") (pinfunction "PA14_76") (pintype "passive"))
    )
    (net (code "102") (name "/TDI") (class "Default")
      (node (ref "J7") (pin "5") (pinfunction "TDI_5") (pintype "passive"))
      (node (ref "U5") (pin "77") (pinfunction "PA15_77") (pintype "passive"))
    )
    (net (code "103") (name "/TDO") (class "Default")
      (node (ref "J7") (pin "13") (pinfunction "TDO_13") (pintype "passive"))
      (node (ref "U5") (pin "89") (pinfunction "PB3_89") (pintype "passive"))
    )
    (net (code "104") (name "/TMS") (class "Default")
      (node (ref "J7") (pin "7") (pinfunction "TMS_7") (pintype "passive"))
      (node (ref "U5") (pin "72") (pinfunction "PA13_72") (pintype "passive"))
    )
    (net (code "105") (name "/TXD1") (class "Default")
      (node (ref "U12") (pin "10") (pinfunction "T2IN_10") (pintype "passive"))
      (node (ref "U3") (pin "4") (pinfunction "DI_4") (pintype "passive"))
      (node (ref "U5") (pin "68") (pinfunction "PA9_68") (pintype "passive"))
    )
    (net (code "106") (name "/TXD2") (class "Default")
      (node (ref "U11") (pin "11") (pinfunction "T1IN_11") (pintype "passive"))
      (node (ref "U5") (pin "25") (pinfunction "PA2_25") (pintype "passive"))
    )
    (net (code "107") (name "/TXD3") (class "Default")
      (node (ref "U11") (pin "10") (pinfunction "T2IN_10") (pintype "passive"))
      (node (ref "U5") (pin "47") (pinfunction "PB10_47") (pintype "passive"))
    )
    (net (code "108") (name "/TXD4") (class "Default")
      (node (ref "U5") (pin "78") (pinfunction "PC10_78") (pintype "passive"))
    )
    (net (code "109") (name "/TXD5") (class "Default")
      (node (ref "U5") (pin "80") (pinfunction "PC12_80") (pintype "passive+no_connect"))
    )
    (net (code "110") (name "/TXD_M1") (class "Default")
      (node (ref "J10") (pin "2") (pinfunction "2_2") (pintype "passive"))
      (node (ref "U12") (pin "8") (pinfunction "R2IN_8") (pintype "passive"))
    )
    (net (code "111") (name "/TXD_M2") (class "Default")
      (node (ref "J9") (pin "2") (pinfunction "2_2") (pintype "passive"))
      (node (ref "U11") (pin "13") (pinfunction "R1IN_13") (pintype "passive"))
    )
    (net (code "112") (name "/TXD_M3") (class "Default")
      (node (ref "J9") (pin "5") (pinfunction "5_5") (pintype "passive"))
      (node (ref "U11") (pin "8") (pinfunction "R2IN_8") (pintype "passive"))
    )
    (net (code "113") (name "/V_check_1") (class "Default")
      (node (ref "U17") (pin "1") (pinfunction "OUT_1") (pintype "open_collector"))
      (node (ref "U5") (pin "2") (pinfunction "PE3_2") (pintype "passive"))
    )
    (net (code "114") (name "/V_check_2") (class "Default")
      (node (ref "U17") (pin "7") (pinfunction "OUT_7") (pintype "open_collector"))
      (node (ref "U5") (pin "1") (pinfunction "PE2_1") (pintype "passive"))
    )
    (net (code "115") (name "/a") (class "Default")
      (node (ref "R91") (pin "1") (pinfunction "1_1") (pintype "passive"))
      (node (ref "U5") (pin "8") (pinfunction "PC14-OSC32_IN_8") (pintype "passive"))
    )
    (net (code "116") (name "/b") (class "Default")
      (node (ref "R90") (pin "1") (pinfunction "1_1") (pintype "passive"))
      (node (ref "U5") (pin "9") (pinfunction "PC15-OSC32_OUT_9") (pintype "passive"))
    )
    (net (code "117") (name "/c") (class "Default")
      (node (ref "R89") (pin "1") (pinfunction "1_1") (pintype "passive"))
      (node (ref "U5") (pin "15") (pinfunction "PC0_15") (pintype "passive"))
    )
    (net (code "118") (name "/check1") (class "Default")
      (node (ref "R108") (pin "1") (pinfunction "1_1") (pintype "passive"))
      (node (ref "U16") (pin "19") (pinfunction "CU-B_19") (pintype "passive"))
      (node (ref "U17") (pin "3") (pinfunction "IN+_3") (pintype "input"))
    )
    (net (code "119") (name "/check2") (class "Default")
      (node (ref "R107") (pin "1") (pinfunction "1_1") (pintype "passive"))
      (node (ref "U16") (pin "2") (pinfunction "CU-A_2") (pintype "passive"))
      (node (ref "U17") (pin "5") (pinfunction "IN+_5") (pintype "input"))
    )
    (net (code "120") (name "/d") (class "Default")
      (node (ref "R88") (pin "1") (pinfunction "1_1") (pintype "passive"))
      (node (ref "U5") (pin "17") (pinfunction "PC2_17") (pintype "passive"))
    )
    (net (code "121") (name "/dp") (class "Default")
      (node (ref "R9") (pin "1") (pinfunction "1_1") (pintype "passive"))
      (node (ref "U5") (pin "16") (pinfunction "PC1_16") (pintype "passive"))
    )
    (net (code "122") (name "/e") (class "Default")
      (node (ref "R87") (pin "1") (pinfunction "1_1") (pintype "passive"))
      (node (ref "U5") (pin "18") (pinfunction "PC3_18") (pintype "passive"))
    )
    (net (code "123") (name "/f") (class "Default")
      (node (ref "R84") (pin "1") (pinfunction "1_1") (pintype "passive"))
      (node (ref "U5") (pin "24") (pinfunction "PA1_24") (pintype "passive"))
    )
    (net (code "124") (name "/g") (class "Default")
      (node (ref "R83") (pin "1") (pinfunction "1_1") (pintype "passive"))
      (node (ref "U5") (pin "23") (pinfunction "PA0-WKUP_23") (pintype "passive"))
    )
    (net (code "125") (name "/heartbeat1") (class "Default")
      (node (ref "R117") (pin "1") (pinfunction "1_1") (pintype "passive"))
      (node (ref "U5") (pin "70") (pinfunction "PA11_70") (pintype "passive"))
    )
    (net (code "126") (name "/heartbeat2") (class "Default")
      (node (ref "R116") (pin "1") (pinfunction "1_1") (pintype "passive"))
      (node (ref "U5") (pin "71") (pinfunction "PA12_71") (pintype "passive"))
    )
    (net (code "127") (name "/key1") (class "Default")
      (node (ref "C68") (pin "1") (pinfunction "1_1") (pintype "passive"))
      (node (ref "R8") (pin "2") (pinfunction "2_2") (pintype "passive"))
      (node (ref "U5") (pin "45") (pinfunction "PE14_45") (pintype "passive"))
      (node (ref "k1") (pin "2") (pinfunction "2_2") (pintype "passive"))
    )
    (net (code "128") (name "/key2") (class "Default")
      (node (ref "C28") (pin "1") (pinfunction "1_1") (pintype "passive"))
      (node (ref "R7") (pin "2") (pinfunction "2_2") (pintype "passive"))
      (node (ref "U5") (pin "46") (pinfunction "PE15_46") (pintype "passive"))
      (node (ref "k2") (pin "2") (pinfunction "2_2") (pintype "passive"))
    )
    (net (code "129") (name "AGND") (class "Default")
      (node (ref "C10") (pin "2") (pinfunction "2_2") (pintype "passive"))
      (node (ref "C13") (pin "2") (pinfunction "2_2") (pintype "passive"))
      (node (ref "C15") (pin "2") (pinfunction "2_2") (pintype "passive"))
      (node (ref "C64") (pin "2") (pinfunction "2_2") (pintype "passive"))
      (node (ref "C65") (pin "2") (pinfunction "2_2") (pintype "passive"))
      (node (ref "C67") (pin "2") (pinfunction "2_2") (pintype "passive"))
      (node (ref "C69") (pin "2") (pinfunction "2_2") (pintype "passive"))
      (node (ref "Q10") (pin "1") (pintype "passive"))
      (node (ref "Q11") (pin "3") (pinfunction "S_3") (pintype "passive"))
      (node (ref "Q3") (pin "2") (pinfunction "S_2") (pintype "input"))
      (node (ref "Q4") (pin "2") (pinfunction "S_2") (pintype "input"))
      (node (ref "Q5") (pin "2") (pinfunction "S_2") (pintype "input"))
      (node (ref "Q6") (pin "3") (pinfunction "S_3") (pintype "passive"))
      (node (ref "Q7") (pin "1") (pintype "passive"))
      (node (ref "Q8") (pin "1") (pintype "passive"))
      (node (ref "Q9") (pin "1") (pintype "passive"))
      (node (ref "R106") (pin "1") (pinfunction "1_1") (pintype "passive"))
      (node (ref "R107") (pin "2") (pinfunction "2_2") (pintype "passive"))
      (node (ref "R108") (pin "2") (pinfunction "2_2") (pintype "passive"))
      (node (ref "R110") (pin "2") (pinfunction "2_2") (pintype "passive"))
      (node (ref "R79") (pin "2") (pinfunction "2_2") (pintype "passive"))
      (node (ref "R80") (pin "2") (pinfunction "2_2") (pintype "passive"))
      (node (ref "R95") (pin "2") (pinfunction "2_2") (pintype "passive"))
      (node (ref "R96") (pin "2") (pinfunction "2_2") (pintype "passive"))
      (node (ref "U16") (pin "1") (pinfunction "GND_1") (pintype "passive"))
      (node (ref "U16") (pin "10") (pinfunction "GND_10") (pintype "passive"))
      (node (ref "U16") (pin "11") (pinfunction "GND_11") (pintype "passive"))
      (node (ref "U16") (pin "20") (pinfunction "GND_20") (pintype "passive"))
    )
    (net (code "130") (name "GND") (class "Default")
      (node (ref "C1") (pin "2") (pinfunction "2_2") (pintype "passive"))
      (node (ref "C11") (pin "2") (pinfunction "2_2") (pintype "passive"))
      (node (ref "C12") (pin "2") (pinfunction "2_2") (pintype "passive"))
      (node (ref "C14") (pin "2") (pinfunction "2_2") (pintype "passive"))
      (node (ref "C16") (pin "2") (pinfunction "2_2") (pintype "passive"))
      (node (ref "C17") (pin "2") (pinfunction "2_2") (pintype "passive"))
      (node (ref "C18") (pin "2") (pinfunction "2_2") (pintype "passive"))
      (node (ref "C19") (pin "2") (pinfunction "2_2") (pintype "passive"))
      (node (ref "C2") (pin "1") (pinfunction "1_1") (pintype "passive"))
      (node (ref "C20") (pin "2") (pinfunction "2_2") (pintype "passive"))
      (node (ref "C21") (pin "1") (pinfunction "1_1") (pintype "passive"))
      (node (ref "C22") (pin "1") (pinfunction "1_1") (pintype "passive"))
      (node (ref "C23") (pin "1") (pinfunction "1_1") (pintype "passive"))
      (node (ref "C24") (pin "1") (pinfunction "1_1") (pintype "passive"))
      (node (ref "C25") (pin "1") (pinfunction "1_1") (pintype "passive"))
      (node (ref "C26") (pin "2") (pinfunction "2_2") (pintype "passive"))
      (node (ref "C27") (pin "1") (pinfunction "1_1") (pintype "passive"))
      (node (ref "C28") (pin "2") (pinfunction "2_2") (pintype "passive"))
      (node (ref "C29") (pin "2") (pinfunction "2_2") (pintype "passive"))
      (node (ref "C3") (pin "2") (pinfunction "2_2") (pintype "passive"))
      (node (ref "C30") (pin "2") (pinfunction "2_2") (pintype "passive"))
      (node (ref "C38") (pin "2") (pinfunction "2_2") (pintype "passive"))
      (node (ref "C39") (pin "2") (pinfunction "2_2") (pintype "passive"))
      (node (ref "C4") (pin "2") (pinfunction "2_2") (pintype "passive"))
      (node (ref "C40") (pin "2") (pinfunction "2_2") (pintype "passive"))
      (node (ref "C41") (pin "2") (pinfunction "2_2") (pintype "passive"))
      (node (ref "C42") (pin "2") (pinfunction "2_2") (pintype "passive"))
      (node (ref "C43") (pin "2") (pinfunction "2_2") (pintype "passive"))
      (node (ref "C44") (pin "2") (pinfunction "2_2") (pintype "passive"))
      (node (ref "C45") (pin "2") (pinfunction "2_2") (pintype "passive"))
      (node (ref "C46") (pin "2") (pinfunction "2_2") (pintype "passive"))
      (node (ref "C47") (pin "2") (pinfunction "2_2") (pintype "passive"))
      (node (ref "C48") (pin "2") (pinfunction "2_2") (pintype "passive"))
      (node (ref "C49") (pin "2") (pinfunction "2_2") (pintype "passive"))
      (node (ref "C5") (pin "1") (pinfunction "1_1") (pintype "passive"))
      (node (ref "C53") (pin "2") (pinfunction "2_2") (pintype "passive"))
      (node (ref "C55") (pin "2") (pinfunction "2_2") (pintype "passive"))
      (node (ref "C59") (pin "2") (pinfunction "2_2") (pintype "passive"))
      (node (ref "C60") (pin "2") (pinfunction "2_2") (pintype "passive"))
      (node (ref "C62") (pin "2") (pinfunction "2_2") (pintype "passive"))
      (node (ref "C63") (pin "2") (pinfunction "2_2") (pintype "passive"))
      (node (ref "C66") (pin "1") (pinfunction "1_1") (pintype "passive"))
      (node (ref "C68") (pin "2") (pinfunction "2_2") (pintype "passive"))
      (node (ref "C69") (pin "1") (pinfunction "1_1") (pintype "passive"))
      (node (ref "C7") (pin "2") (pinfunction "2_2") (pintype "passive"))
      (node (ref "C8") (pin "2") (pinfunction "2_2") (pintype "passive"))
      (node (ref "C9") (pin "2") (pinfunction "2_2") (pintype "passive"))
      (node (ref "D10") (pin "2") (pinfunction "K_2") (pintype "passive"))
      (node (ref "D12") (pin "1") (pinfunction "A_1") (pintype "passive"))
      (node (ref "D13") (pin "1") (pinfunction "A_1") (pintype "passive"))
      (node (ref "D22") (pin "2") (pinfunction "K_2") (pintype "passive"))
      (node (ref "D23") (pin "2") (pinfunction "K_2") (pintype "passive"))
      (node (ref "D24") (pin "2") (pinfunction "K_2") (pintype "passive"))
      (node (ref "D25") (pin "2") (pinfunction "K_2") (pintype "passive"))
      (node (ref "D26") (pin "2") (pinfunction "K_2") (pintype "passive"))
      (node (ref "D27") (pin "2") (pinfunction "K_2") (pintype "passive"))
      (node (ref "D28") (pin "2") (pinfunction "K_2") (pintype "passive"))
      (node (ref "D29") (pin "2") (pinfunction "K_2") (pintype "passive"))
      (node (ref "D30") (pin "2") (pinfunction "K_2") (pintype "passive"))
      (node (ref "D31") (pin "2") (pinfunction "K_2") (pintype "passive"))
      (node (ref "D32") (pin "2") (pinfunction "K_2") (pintype "passive"))
      (node (ref "D33") (pin "2") (pinfunction "K_2") (pintype "passive"))
      (node (ref "D50") (pin "2") (pinfunction "K_2") (pintype "passive"))
      (node (ref "D51") (pin "2") (pinfunction "K_2") (pintype "passive"))
      (node (ref "D8") (pin "2") (pinfunction "K_2") (pintype "passive"))
      (node (ref "D9") (pin "2") (pinfunction "K_2") (pintype "passive"))
      (node (ref "J1") (pin "15") (pinfunction "15_15") (pintype "passive"))
      (node (ref "J10") (pin "3") (pinfunction "3_3") (pintype "passive"))
      (node (ref "J11") (pin "2") (pinfunction "2_2") (pintype "passive"))
      (node (ref "J2") (pin "2") (pinfunction "2_2") (pintype "passive"))
      (node (ref "J2") (pin "4") (pinfunction "4_4") (pintype "passive"))
      (node (ref "J20") (pin "10") (pinfunction "10_10") (pintype "passive"))
      (node (ref "J20") (pin "12") (pinfunction "12_12") (pintype "passive"))
      (node (ref "J20") (pin "2") (pinfunction "2_2") (pintype "passive"))
      (node (ref "J20") (pin "4") (pinfunction "4_4") (pintype "passive"))
      (node (ref "J20") (pin "6") (pinfunction "6_6") (pintype "passive"))
      (node (ref "J20") (pin "8") (pinfunction "8_8") (pintype "passive"))
      (node (ref "J3") (pin "2") (pinfunction "2_2") (pintype "passive"))
      (node (ref "J3") (pin "4") (pinfunction "4_4") (pintype "passive"))
      (node (ref "J4") (pin "1") (pinfunction "1_1") (pintype "passive"))
      (node (ref "J4") (pin "11") (pinfunction "11_11") (pintype "passive"))
      (node (ref "J4") (pin "13") (pinfunction "13_13") (pintype "passive"))
      (node (ref "J4") (pin "15") (pinfunction "15_15") (pintype "passive"))
      (node (ref "J4") (pin "17") (pinfunction "17_17") (pintype "passive"))
      (node (ref "J4") (pin "3") (pinfunction "3_3") (pintype "passive"))
      (node (ref "J4") (pin "5") (pinfunction "5_5") (pintype "passive"))
      (node (ref "J4") (pin "7") (pinfunction "7_7") (pintype "passive"))
      (node (ref "J4") (pin "9") (pinfunction "9_9") (pintype "passive"))
      (node (ref "J5") (pin "1") (pinfunction "1_1") (pintype "passive"))
      (node (ref "J5") (pin "11") (pinfunction "11_11") (pintype "passive"))
      (node (ref "J5") (pin "13") (pinfunction "13_13") (pintype "passive"))
      (node (ref "J5") (pin "15") (pinfunction "15_15") (pintype "passive"))
      (node (ref "J5") (pin "17") (pinfunction "17_17") (pintype "passive"))
      (node (ref "J5") (pin "3") (pinfunction "3_3") (pintype "passive"))
      (node (ref "J5") (pin "5") (pinfunction "5_5") (pintype "passive"))
      (node (ref "J5") (pin "7") (pinfunction "7_7") (pintype "passive"))
      (node (ref "J5") (pin "9") (pinfunction "9_9") (pintype "passive"))
      (node (ref "J6") (pin "1") (pinfunction "1_1") (pintype "passive"))
      (node (ref "J6") (pin "11") (pinfunction "11_11") (pintype "passive"))
      (node (ref "J6") (pin "13") (pinfunction "13_13") (pintype "passive"))
      (node (ref "J6") (pin "15") (pinfunction "15_15") (pintype "passive"))
      (node (ref "J6") (pin "17") (pinfunction "17_17") (pintype "passive"))
      (node (ref "J6") (pin "3") (pinfunction "3_3") (pintype "passive"))
      (node (ref "J6") (pin "5") (pinfunction "5_5") (pintype "passive"))
      (node (ref "J6") (pin "7") (pinfunction "7_7") (pintype "passive"))
      (node (ref "J6") (pin "9") (pinfunction "9_9") (pintype "passive"))
      (node (ref "J7") (pin "10") (pinfunction "GND_10") (pintype "passive"))
      (node (ref "J7") (pin "12") (pinfunction "GND_12") (pintype "passive"))
      (node (ref "J7") (pin "14") (pinfunction "GND_14") (pintype "passive"))
      (node (ref "J7") (pin "16") (pinfunction "GND_16") (pintype "passive"))
      (node (ref "J7") (pin "18") (pinfunction "GND_18") (pintype "passive"))
      (node (ref "J7") (pin "20") (pinfunction "GND_20") (pintype "passive"))
      (node (ref "J7") (pin "4") (pinfunction "GND_4") (pintype "passive"))
      (node (ref "J7") (pin "6") (pinfunction "GND_6") (pintype "passive"))
      (node (ref "J7") (pin "8") (pinfunction "GND_8") (pintype "passive"))
      (node (ref "J8") (pin "1") (pinfunction "1_1") (pintype "passive"))
      (node (ref "J8") (pin "11") (pinfunction "11_11") (pintype "passive"))
      (node (ref "J8") (pin "13") (pinfunction "13_13") (pintype "passive"))
      (node (ref "J8") (pin "15") (pinfunction "15_15") (pintype "passive"))
      (node (ref "J8") (pin "17") (pinfunction "17_17") (pintype "passive"))
      (node (ref "J8") (pin "3") (pinfunction "3_3") (pintype "passive"))
      (node (ref "J8") (pin "5") (pinfunction "5_5") (pintype "passive"))
      (node (ref "J8") (pin "7") (pinfunction "7_7") (pintype "passive"))
      (node (ref "J8") (pin "9") (pinfunction "9_9") (pintype "passive"))
      (node (ref "J9") (pin "3") (pinfunction "3_3") (pintype "passive"))
      (node (ref "J9") (pin "6") (pinfunction "6_6") (pintype "passive"))
      (node (ref "K3") (pin "1") (pinfunction "1_1") (pintype "passive"))
      (node (ref "R100") (pin "1") (pinfunction "1_1") (pintype "passive"))
      (node (ref "R101") (pin "1") (pinfunction "1_1") (pintype "passive"))
      (node (ref "R106") (pin "2") (pinfunction "2_2") (pintype "passive"))
      (node (ref "R109") (pin "2") (pinfunction "2_2") (pintype "passive"))
      (node (ref "R111") (pin "2") (pinfunction "2_2") (pintype "passive"))
      (node (ref "R118") (pin "1") (pinfunction "1_1") (pintype "passive"))
      (node (ref "R23") (pin "2") (pinfunction "2_2") (pintype "passive"))
      (node (ref "R24") (pin "1") (pinfunction "1_1") (pintype "passive"))
      (node (ref "R56") (pin "1") (pinfunction "1_1") (pintype "passive"))
      (node (ref "R58") (pin "1") (pinfunction "1_1") (pintype "passive"))
      (node (ref "R64") (pin "1") (pinfunction "1_1") (pintype "passive"))
      (node (ref "R77") (pin "2") (pinfunction "2_2") (pintype "passive"))
      (node (ref "R78") (pin "2") (pinfunction "2_2") (pintype "passive"))
      (node (ref "R92") (pin "2") (pinfunction "2_2") (pintype "passive"))
      (node (ref "R93") (pin "2") (pinfunction "2_2") (pintype "passive"))
      (node (ref "R94") (pin "1") (pinfunction "1_1") (pintype "passive"))
      (node (ref "R99") (pin "1") (pinfunction "1_1") (pintype "passive"))
      (node (ref "U1") (pin "2") (pinfunction "GND_2") (pintype "passive"))
      (node (ref "U11") (pin "15") (pinfunction "GND_15") (pintype "passive"))
      (node (ref "U12") (pin "15") (pinfunction "GND_15") (pintype "passive"))
      (node (ref "U14") (pin "7") (pinfunction "GND_7") (pintype "passive"))
      (node (ref "U15") (pin "7") (pinfunction "GND_7") (pintype "passive"))
      (node (ref "U17") (pin "4") (pinfunction "V-_4") (pintype "power_in"))
      (node (ref "U2") (pin "0") (pinfunction "GND_0") (pintype "passive"))
      (node (ref "U2") (pin "3") (pinfunction "GND_3") (pintype "passive"))
      (node (ref "U2") (pin "5") (pinfunction "/ON_5") (pintype "passive"))
      (node (ref "U3") (pin "5") (pinfunction "GND_5") (pintype "passive"))
      (node (ref "U5") (pin "10") (pinfunction "VSS_5_10") (pintype "passive"))
      (node (ref "U5") (pin "19") (pinfunction "VSSA_19") (pintype "passive"))
      (node (ref "U5") (pin "20") (pinfunction "VREF-_20") (pintype "passive"))
      (node (ref "U5") (pin "27") (pinfunction "VSS_4_27") (pintype "passive"))
      (node (ref "U5") (pin "49") (pinfunction "VSS_1_49") (pintype "passive"))
      (node (ref "U5") (pin "74") (pinfunction "VSS_2_74") (pintype "passive"))
      (node (ref "U5") (pin "99") (pinfunction "VSS_3_99") (pintype "passive"))
      (node (ref "U6") (pin "1") (pinfunction "GND_1") (pintype "passive"))
      (node (ref "U7") (pin "4") (pinfunction "GND_4") (pintype "passive"))
      (node (ref "U9") (pin "8") (pinfunction "GND_8") (pintype "passive"))
      (node (ref "k1") (pin "1") (pinfunction "1_1") (pintype "passive"))
      (node (ref "k2") (pin "1") (pinfunction "1_1") (pintype "passive"))
    )
    (net (code "131") (name "Net-(D2-A)") (class "Default")
      (node (ref "D2") (pin "1") (pinfunction "A_1") (pintype "passive"))
      (node (ref "R17") (pin "2") (pinfunction "2_2") (pintype "passive"))
    )
    (net (code "132") (name "Net-(D3-A)") (class "Default")
      (node (ref "D3") (pin "1") (pinfunction "A_1") (pintype "passive"))
      (node (ref "R18") (pin "2") (pinfunction "2_2") (pintype "passive"))
    )
    (net (code "133") (name "Net-(D4-A)") (class "Default")
      (node (ref "D4") (pin "1") (pinfunction "A_1") (pintype "passive"))
      (node (ref "R19") (pin "2") (pinfunction "2_2") (pintype "passive"))
    )
    (net (code "134") (name "Net-(D5-A)") (class "Default")
      (node (ref "D5") (pin "1") (pinfunction "A_1") (pintype "passive"))
      (node (ref "R20") (pin "2") (pinfunction "2_2") (pintype "passive"))
    )
    (net (code "135") (name "Net-(D6-A)") (class "Default")
      (node (ref "D6") (pin "1") (pinfunction "A_1") (pintype "passive"))
      (node (ref "R21") (pin "2") (pinfunction "2_2") (pintype "passive"))
    )
    (net (code "136") (name "Net-(D7-A)") (class "Default")
      (node (ref "D7") (pin "1") (pinfunction "A_1") (pintype "passive"))
      (node (ref "R22") (pin "2") (pinfunction "2_2") (pintype "passive"))
    )
    (net (code "137") (name "Net-(D8-A)") (class "Default")
      (node (ref "D8") (pin "1") (pinfunction "A_1") (pintype "passive"))
      (node (ref "R14") (pin "2") (pinfunction "2_2") (pintype "passive"))
    )
    (net (code "138") (name "Net-(D9-A)") (class "Default")
      (node (ref "D9") (pin "1") (pinfunction "A_1") (pintype "passive"))
      (node (ref "R15") (pin "2") (pinfunction "2_2") (pintype "passive"))
    )
    (net (code "139") (name "Net-(D10-A)") (class "Default")
      (node (ref "D10") (pin "1") (pinfunction "A_1") (pintype "passive"))
      (node (ref "R16") (pin "2") (pinfunction "2_2") (pintype "passive"))
    )
    (net (code "140") (name "Net-(D11-A)") (class "Default")
      (node (ref "C12") (pin "1") (pinfunction "1_1") (pintype "passive"))
      (node (ref "C7") (pin "1") (pinfunction "1_1") (pintype "passive"))
      (node (ref "D11") (pin "1") (pinfunction "A_1") (pintype "passive"))
      (node (ref "F1") (pin "2") (pinfunction "2_2") (pintype "passive"))
    )
    (net (code "141") (name "Net-(D12-K)") (class "Default")
      (node (ref "D12") (pin "2") (pinfunction "K_2") (pintype "passive"))
      (node (ref "L1") (pin "1") (pinfunction "1_1") (pintype "passive"))
      (node (ref "U2") (pin "2") (pinfunction "OUT_2") (pintype "passive"))
    )
    (net (code "142") (name "Net-(D14-A)") (class "Default")
      (node (ref "D14") (pin "1") (pinfunction "A_1") (pintype "passive"))
      (node (ref "R49") (pin "1") (pinfunction "1_1") (pintype "passive"))
    )
    (net (code "143") (name "Net-(D16-A)") (class "Default")
      (node (ref "D16") (pin "1") (pinfunction "A_1") (pintype "passive"))
      (node (ref "R50") (pin "1") (pinfunction "1_1") (pintype "passive"))
    )
    (net (code "144") (name "Net-(D17-A)") (class "Default")
      (node (ref "D17") (pin "1") (pinfunction "A_1") (pintype "passive"))
      (node (ref "R51") (pin "1") (pinfunction "1_1") (pintype "passive"))
    )
    (net (code "145") (name "Net-(D18-A)") (class "Default")
      (node (ref "D18") (pin "1") (pinfunction "A_1") (pintype "passive"))
      (node (ref "R52") (pin "1") (pinfunction "1_1") (pintype "passive"))
    )
    (net (code "146") (name "Net-(D19-A)") (class "Default")
      (node (ref "D19") (pin "1") (pinfunction "A_1") (pintype "passive"))
      (node (ref "R53") (pin "1") (pinfunction "1_1") (pintype "passive"))
    )
    (net (code "147") (name "Net-(D20-A)") (class "Default")
      (node (ref "D20") (pin "1") (pinfunction "A_1") (pintype "passive"))
      (node (ref "R54") (pin "1") (pinfunction "1_1") (pintype "passive"))
    )
    (net (code "148") (name "Net-(D21-A)") (class "Default")
      (node (ref "D21") (pin "1") (pinfunction "A_1") (pintype "passive"))
      (node (ref "R55") (pin "1") (pinfunction "1_1") (pintype "passive"))
    )
    (net (code "149") (name "Net-(D22-A)") (class "Default")
      (node (ref "D22") (pin "1") (pinfunction "A_1") (pintype "passive"))
      (node (ref "R65") (pin "2") (pinfunction "2_2") (pintype "passive"))
    )
    (net (code "150") (name "Net-(D23-A)") (class "Default")
      (node (ref "D23") (pin "1") (pinfunction "A_1") (pintype "passive"))
      (node (ref "R66") (pin "2") (pinfunction "2_2") (pintype "passive"))
    )
    (net (code "151") (name "Net-(D24-A)") (class "Default")
      (node (ref "D24") (pin "1") (pinfunction "A_1") (pintype "passive"))
      (node (ref "R67") (pin "2") (pinfunction "2_2") (pintype "passive"))
    )
    (net (code "152") (name "Net-(D25-A)") (class "Default")
      (node (ref "D25") (pin "1") (pinfunction "A_1") (pintype "passive"))
      (node (ref "R68") (pin "2") (pinfunction "2_2") (pintype "passive"))
    )
    (net (code "153") (name "Net-(D26-A)") (class "Default")
      (node (ref "D26") (pin "1") (pinfunction "A_1") (pintype "passive"))
      (node (ref "R69") (pin "2") (pinfunction "2_2") (pintype "passive"))
    )
    (net (code "154") (name "Net-(D27-A)") (class "Default")
      (node (ref "D27") (pin "1") (pinfunction "A_1") (pintype "passive"))
      (node (ref "R70") (pin "2") (pinfunction "2_2") (pintype "passive"))
    )
    (net (code "155") (name "Net-(D28-A)") (class "Default")
      (node (ref "D28") (pin "1") (pinfunction "A_1") (pintype "passive"))
      (node (ref "R71") (pin "2") (pinfunction "2_2") (pintype "passive"))
    )
    (net (code "156") (name "Net-(D29-A)") (class "Default")
      (node (ref "D29") (pin "1") (pinfunction "A_1") (pintype "passive"))
      (node (ref "R72") (pin "2") (pinfunction "2_2") (pintype "passive"))
    )
    (net (code "157") (name "Net-(D30-A)") (class "Default")
      (node (ref "D30") (pin "1") (pinfunction "A_1") (pintype "passive"))
      (node (ref "R73") (pin "2") (pinfunction "2_2") (pintype "passive"))
    )
    (net (code "158") (name "Net-(D31-A)") (class "Default")
      (node (ref "D31") (pin "1") (pinfunction "A_1") (pintype "passive"))
      (node (ref "R74") (pin "2") (pinfunction "2_2") (pintype "passive"))
    )
    (net (code "159") (name "Net-(D32-A)") (class "Default")
      (node (ref "D32") (pin "1") (pinfunction "A_1") (pintype "passive"))
      (node (ref "R75") (pin "2") (pinfunction "2_2") (pintype "passive"))
    )
    (net (code "160") (name "Net-(D33-A)") (class "Default")
      (node (ref "D33") (pin "1") (pinfunction "A_1") (pintype "passive"))
      (node (ref "R76") (pin "2") (pinfunction "2_2") (pintype "passive"))
    )
    (net (code "161") (name "Net-(D34-A)") (class "Default")
      (node (ref "D34") (pin "1") (pinfunction "A_1") (pintype "passive"))
      (node (ref "R85") (pin "2") (pinfunction "2_2") (pintype "passive"))
    )
    (net (code "162") (name "Net-(D34-K)") (class "Default")
      (node (ref "D34") (pin "2") (pinfunction "K_2") (pintype "passive"))
      (node (ref "D39") (pin "A") (pinfunction "A_A") (pintype "passive"))
      (node (ref "J14") (pin "2") (pinfunction "2_2") (pintype "passive"))
      (node (ref "Q3") (pin "3") (pinfunction "D_3") (pintype "input"))
      (node (ref "R81") (pin "2") (pinfunction "2_2") (pintype "passive"))
    )
    (net (code "163") (name "Net-(D35-A)") (class "Default")
      (node (ref "D35") (pin "1") (pinfunction "A_1") (pintype "passive"))
      (node (ref "R86") (pin "2") (pinfunction "2_2") (pintype "passive"))
    )
    (net (code "164") (name "Net-(D35-K)") (class "Default")
      (node (ref "D35") (pin "2") (pinfunction "K_2") (pintype "passive"))
      (node (ref "D40") (pin "A") (pinfunction "A_A") (pintype "passive"))
      (node (ref "J15") (pin "2") (pinfunction "2_2") (pintype "passive"))
      (node (ref "Q4") (pin "3") (pinfunction "D_3") (pintype "input"))
      (node (ref "R82") (pin "2") (pinfunction "2_2") (pintype "passive"))
    )
    (net (code "165") (name "Net-(D36-A)") (class "Default")
      (node (ref "D36") (pin "1") (pinfunction "A_1") (pintype "passive"))
      (node (ref "R102") (pin "2") (pinfunction "2_2") (pintype "passive"))
    )
    (net (code "166") (name "Net-(D36-K)") (class "Default")
      (node (ref "D36") (pin "2") (pinfunction "K_2") (pintype "passive"))
      (node (ref "D41") (pin "A") (pinfunction "A_A") (pintype "passive"))
      (node (ref "J16") (pin "2") (pinfunction "2_2") (pintype "passive"))
      (node (ref "Q5") (pin "3") (pinfunction "D_3") (pintype "input"))
      (node (ref "R97") (pin "2") (pinfunction "2_2") (pintype "passive"))
    )
    (net (code "167") (name "Net-(D37-A)") (class "Default")
      (node (ref "D37") (pin "1") (pinfunction "A_1") (pintype "passive"))
      (node (ref "R103") (pin "2") (pinfunction "2_2") (pintype "passive"))
    )
    (net (code "168") (name "Net-(D37-K)") (class "Default")
      (node (ref "D37") (pin "2") (pinfunction "K_2") (pintype "passive"))
      (node (ref "D42") (pin "A") (pinfunction "A_A") (pintype "passive"))
      (node (ref "J17") (pin "2") (pinfunction "2_2") (pintype "passive"))
      (node (ref "Q6") (pin "2") (pinfunction "D_2") (pintype "passive"))
      (node (ref "R98") (pin "2") (pinfunction "2_2") (pintype "passive"))
    )
    (net (code "169") (name "Net-(D38-A)") (class "Default")
      (node (ref "D38") (pin "1") (pinfunction "A_1") (pintype "passive"))
      (node (ref "R114") (pin "2") (pinfunction "2_2") (pintype "passive"))
    )
    (net (code "170") (name "Net-(D38-K)") (class "Default")
      (node (ref "D38") (pin "2") (pinfunction "K_2") (pintype "passive"))
      (node (ref "D43") (pin "A") (pinfunction "A_A") (pintype "passive"))
      (node (ref "J19") (pin "2") (pinfunction "2_2") (pintype "passive"))
      (node (ref "Q11") (pin "2") (pinfunction "D_2") (pintype "passive"))
      (node (ref "R112") (pin "2") (pinfunction "2_2") (pintype "passive"))
    )
    (net (code "171") (name "Net-(D50-A)") (class "Default")
      (node (ref "D50") (pin "1") (pinfunction "A_1") (pintype "passive"))
      (node (ref "R116") (pin "2") (pinfunction "2_2") (pintype "passive"))
    )
    (net (code "172") (name "Net-(D51-A)") (class "Default")
      (node (ref "D51") (pin "1") (pinfunction "A_1") (pintype "passive"))
      (node (ref "R117") (pin "2") (pinfunction "2_2") (pintype "passive"))
    )
    (net (code "173") (name "Net-(DS1-DP)") (class "Default")
      (node (ref "DS1") (pin "7") (pinfunction "DP_7") (pintype "passive"))
      (node (ref "R9") (pin "2") (pinfunction "2_2") (pintype "passive"))
    )
    (net (code "174") (name "Net-(DS1-a)") (class "Default")
      (node (ref "DS1") (pin "10") (pinfunction "a_10") (pintype "passive"))
      (node (ref "R91") (pin "2") (pinfunction "2_2") (pintype "passive"))
    )
    (net (code "175") (name "Net-(DS1-b)") (class "Default")
      (node (ref "DS1") (pin "9") (pinfunction "b_9") (pintype "passive"))
      (node (ref "R90") (pin "2") (pinfunction "2_2") (pintype "passive"))
    )
    (net (code "176") (name "Net-(DS1-c)") (class "Default")
      (node (ref "DS1") (pin "8") (pinfunction "c_8") (pintype "passive"))
      (node (ref "R89") (pin "2") (pinfunction "2_2") (pintype "passive"))
    )
    (net (code "177") (name "Net-(DS1-d)") (class "Default")
      (node (ref "DS1") (pin "5") (pinfunction "d_5") (pintype "passive"))
      (node (ref "R88") (pin "2") (pinfunction "2_2") (pintype "passive"))
    )
    (net (code "178") (name "Net-(DS1-e)") (class "Default")
      (node (ref "DS1") (pin "4") (pinfunction "e_4") (pintype "passive"))
      (node (ref "R87") (pin "2") (pinfunction "2_2") (pintype "passive"))
    )
    (net (code "179") (name "Net-(DS1-f)") (class "Default")
      (node (ref "DS1") (pin "2") (pinfunction "f_2") (pintype "passive"))
      (node (ref "R84") (pin "2") (pinfunction "2_2") (pintype "passive"))
    )
    (net (code "180") (name "Net-(DS1-g)") (class "Default")
      (node (ref "DS1") (pin "3") (pinfunction "g_3") (pintype "passive"))
      (node (ref "R83") (pin "2") (pinfunction "2_2") (pintype "passive"))
    )
    (net (code "181") (name "Net-(J4-Pad2)") (class "Default")
      (node (ref "J4") (pin "2") (pinfunction "2_2") (pintype "passive"))
      (node (ref "R37") (pin "2") (pinfunction "2_2") (pintype "passive"))
    )
    (net (code "182") (name "Net-(J4-Pad8)") (class "Default")
      (node (ref "J4") (pin "8") (pinfunction "8_8") (pintype "passive"))
      (node (ref "R39") (pin "2") (pinfunction "2_2") (pintype "passive"))
    )
    (net (code "183") (name "Net-(J4-Pad14)") (class "Default")
      (node (ref "J4") (pin "14") (pinfunction "14_14") (pintype "passive"))
      (node (ref "R41") (pin "2") (pinfunction "2_2") (pintype "passive"))
    )
    (net (code "184") (name "Net-(J5-Pad2)") (class "Default")
      (node (ref "J5") (pin "2") (pinfunction "2_2") (pintype "passive"))
      (node (ref "R31") (pin "2") (pinfunction "2_2") (pintype "passive"))
    )
    (net (code "185") (name "Net-(J5-Pad8)") (class "Default")
      (node (ref "J5") (pin "8") (pinfunction "8_8") (pintype "passive"))
      (node (ref "R33") (pin "2") (pinfunction "2_2") (pintype "passive"))
    )
    (net (code "186") (name "Net-(J5-Pad14)") (class "Default")
      (node (ref "J5") (pin "14") (pinfunction "14_14") (pintype "passive"))
      (node (ref "R35") (pin "2") (pinfunction "2_2") (pintype "passive"))
    )
    (net (code "187") (name "Net-(J6-Pad2)") (class "Default")
      (node (ref "J6") (pin "2") (pinfunction "2_2") (pintype "passive"))
      (node (ref "R25") (pin "2") (pinfunction "2_2") (pintype "passive"))
    )
    (net (code "188") (name "Net-(J6-Pad8)") (class "Default")
      (node (ref "J6") (pin "8") (pinfunction "8_8") (pintype "passive"))
      (node (ref "R27") (pin "2") (pinfunction "2_2") (pintype "passive"))
    )
    (net (code "189") (name "Net-(J6-Pad14)") (class "Default")
      (node (ref "J6") (pin "14") (pinfunction "14_14") (pintype "passive"))
      (node (ref "R29") (pin "2") (pinfunction "2_2") (pintype "passive"))
    )
    (net (code "190") (name "Net-(J8-Pad2)") (class "Default")
      (node (ref "J8") (pin "2") (pinfunction "2_2") (pintype "passive"))
      (node (ref "R43") (pin "2") (pinfunction "2_2") (pintype "passive"))
    )
    (net (code "191") (name "Net-(J8-Pad8)") (class "Default")
      (node (ref "J8") (pin "8") (pinfunction "8_8") (pintype "passive"))
      (node (ref "R45") (pin "2") (pinfunction "2_2") (pintype "passive"))
    )
    (net (code "192") (name "Net-(J8-Pad14)") (class "Default")
      (node (ref "J8") (pin "14") (pinfunction "14_14") (pintype "passive"))
      (node (ref "R47") (pin "2") (pinfunction "2_2") (pintype "passive"))
    )
    (net (code "193") (name "Net-(P1-E)") (class "Default")
      (node (ref "P1") (pin "3") (pinfunction "E_3") (pintype "passive"))
      (node (ref "R118") (pin "2") (pinfunction "2_2") (pintype "passive"))
    )
    (net (code "194") (name "Net-(P1-K)") (class "Default")
      (node (ref "P1") (pin "2") (pinfunction "K_2") (pintype "passive"))
      (node (ref "R23") (pin "1") (pinfunction "1_1") (pintype "passive"))
    )
    (net (code "195") (name "Net-(P4-C)") (class "Default")
      (node (ref "P4") (pin "4") (pinfunction "C_4") (pintype "passive"))
      (node (ref "R81") (pin "1") (pinfunction "1_1") (pintype "passive"))
    )
    (net (code "196") (name "Net-(P4-E)") (class "Default")
      (node (ref "P4") (pin "3") (pinfunction "E_3") (pintype "passive"))
      (node (ref "Q3") (pin "1") (pinfunction "G_1") (pintype "input"))
      (node (ref "R79") (pin "1") (pinfunction "1_1") (pintype "passive"))
    )
    (net (code "197") (name "Net-(P4-K)") (class "Default")
      (node (ref "P4") (pin "2") (pinfunction "K_2") (pintype "passive"))
      (node (ref "R77") (pin "1") (pinfunction "1_1") (pintype "passive"))
    )
    (net (code "198") (name "Net-(P5-C)") (class "Default")
      (node (ref "P5") (pin "4") (pinfunction "C_4") (pintype "passive"))
      (node (ref "R82") (pin "1") (pinfunction "1_1") (pintype "passive"))
    )
    (net (code "199") (name "Net-(P5-E)") (class "Default")
      (node (ref "P5") (pin "3") (pinfunction "E_3") (pintype "passive"))
      (node (ref "Q4") (pin "1") (pinfunction "G_1") (pintype "input"))
      (node (ref "R80") (pin "1") (pinfunction "1_1") (pintype "passive"))
    )
    (net (code "200") (name "Net-(P5-K)") (class "Default")
      (node (ref "P5") (pin "2") (pinfunction "K_2") (pintype "passive"))
      (node (ref "R78") (pin "1") (pinfunction "1_1") (pintype "passive"))
    )
    (net (code "201") (name "Net-(P6-C)") (class "Default")
      (node (ref "P6") (pin "4") (pinfunction "C_4") (pintype "passive"))
      (node (ref "R97") (pin "1") (pinfunction "1_1") (pintype "passive"))
    )
    (net (code "202") (name "Net-(P6-E)") (class "Default")
      (node (ref "P6") (pin "3") (pinfunction "E_3") (pintype "passive"))
      (node (ref "Q5") (pin "1") (pinfunction "G_1") (pintype "input"))
      (node (ref "R95") (pin "1") (pinfunction "1_1") (pintype "passive"))
    )
    (net (code "203") (name "Net-(P6-K)") (class "Default")
      (node (ref "P6") (pin "2") (pinfunction "K_2") (pintype "passive"))
      (node (ref "R92") (pin "1") (pinfunction "1_1") (pintype "passive"))
    )
    (net (code "204") (name "Net-(P7-C)") (class "Default")
      (node (ref "P7") (pin "4") (pinfunction "C_4") (pintype "passive"))
      (node (ref "R98") (pin "1") (pinfunction "1_1") (pintype "passive"))
    )
    (net (code "205") (name "Net-(P7-E)") (class "Default")
      (node (ref "P7") (pin "3") (pinfunction "E_3") (pintype "passive"))
      (node (ref "Q6") (pin "1") (pinfunction "G_1") (pintype "passive"))
      (node (ref "R96") (pin "1") (pinfunction "1_1") (pintype "passive"))
    )
    (net (code "206") (name "Net-(P7-K)") (class "Default")
      (node (ref "P7") (pin "2") (pinfunction "K_2") (pintype "passive"))
      (node (ref "R93") (pin "1") (pinfunction "1_1") (pintype "passive"))
    )
    (net (code "207") (name "Net-(P8-C)") (class "Default")
      (node (ref "P8") (pin "4") (pinfunction "C_4") (pintype "passive"))
      (node (ref "R112") (pin "1") (pinfunction "1_1") (pintype "passive"))
    )
    (net (code "208") (name "Net-(P8-E)") (class "Default")
      (node (ref "P8") (pin "3") (pinfunction "E_3") (pintype "passive"))
      (node (ref "Q11") (pin "1") (pinfunction "G_1") (pintype "passive"))
      (node (ref "R110") (pin "1") (pinfunction "1_1") (pintype "passive"))
    )
    (net (code "209") (name "Net-(P8-K)") (class "Default")
      (node (ref "P8") (pin "2") (pinfunction "K_2") (pintype "passive"))
      (node (ref "R109") (pin "1") (pinfunction "1_1") (pintype "passive"))
    )
    (net (code "210") (name "Net-(U11-C1+)") (class "Default")
      (node (ref "C32") (pin "2") (pinfunction "2_2") (pintype "passive"))
      (node (ref "U11") (pin "1") (pinfunction "C1+_1") (pintype "passive"))
    )
    (net (code "211") (name "Net-(U11-C1-)") (class "Default")
      (node (ref "C32") (pin "1") (pinfunction "1_1") (pintype "passive"))
      (node (ref "U11") (pin "3") (pinfunction "C1-_3") (pintype "passive"))
    )
    (net (code "212") (name "Net-(U11-C2+)") (class "Default")
      (node (ref "C33") (pin "1") (pinfunction "1_1") (pintype "passive"))
      (node (ref "U11") (pin "4") (pinfunction "C2+_4") (pintype "passive"))
    )
    (net (code "213") (name "Net-(U11-C2-)") (class "Default")
      (node (ref "C33") (pin "2") (pinfunction "2_2") (pintype "passive"))
      (node (ref "U11") (pin "5") (pinfunction "C2-_5") (pintype "passive"))
    )
    (net (code "214") (name "Net-(U11-V+)") (class "Default")
      (node (ref "C52") (pin "1") (pinfunction "1_1") (pintype "passive"))
      (node (ref "U11") (pin "2") (pinfunction "V+_2") (pintype "passive"))
    )
    (net (code "215") (name "Net-(U11-V-)") (class "Default")
      (node (ref "C53") (pin "1") (pinfunction "1_1") (pintype "passive"))
      (node (ref "U11") (pin "6") (pinfunction "V-_6") (pintype "passive"))
    )
    (net (code "216") (name "Net-(U12-C1+)") (class "Default")
      (node (ref "C34") (pin "2") (pinfunction "2_2") (pintype "passive"))
      (node (ref "U12") (pin "1") (pinfunction "C1+_1") (pintype "passive"))
    )
    (net (code "217") (name "Net-(U12-C1-)") (class "Default")
      (node (ref "C34") (pin "1") (pinfunction "1_1") (pintype "passive"))
      (node (ref "U12") (pin "3") (pinfunction "C1-_3") (pintype "passive"))
    )
    (net (code "218") (name "Net-(U12-C2+)") (class "Default")
      (node (ref "C35") (pin "1") (pinfunction "1_1") (pintype "passive"))
      (node (ref "U12") (pin "4") (pinfunction "C2+_4") (pintype "passive"))
    )
    (net (code "219") (name "Net-(U12-C2-)") (class "Default")
      (node (ref "C35") (pin "2") (pinfunction "2_2") (pintype "passive"))
      (node (ref "U12") (pin "5") (pinfunction "C2-_5") (pintype "passive"))
    )
    (net (code "220") (name "Net-(U12-V+)") (class "Default")
      (node (ref "C54") (pin "1") (pinfunction "1_1") (pintype "passive"))
      (node (ref "U12") (pin "2") (pinfunction "V+_2") (pintype "passive"))
    )
    (net (code "221") (name "Net-(U12-V-)") (class "Default")
      (node (ref "C55") (pin "1") (pinfunction "1_1") (pintype "passive"))
      (node (ref "U12") (pin "6") (pinfunction "V-_6") (pintype "passive"))
    )
    (net (code "222") (name "Net-(U16-ENA)") (class "Default")
      (node (ref "C66") (pin "2") (pinfunction "2_2") (pintype "passive"))
      (node (ref "R104") (pin "2") (pinfunction "2_2") (pintype "passive"))
      (node (ref "U16") (pin "8") (pinfunction "ENA_8") (pintype "passive"))
    )
    (net (code "223") (name "Net-(U16-ENB)") (class "Default")
      (node (ref "C64") (pin "1") (pinfunction "1_1") (pintype "passive"))
      (node (ref "R105") (pin "2") (pinfunction "2_2") (pintype "passive"))
      (node (ref "U16") (pin "14") (pinfunction "ENB_14") (pintype "passive"))
    )
    (net (code "224") (name "Net-(U17A-IN-)") (class "Default")
      (node (ref "R111") (pin "1") (pinfunction "1_1") (pintype "passive"))
      (node (ref "R113") (pin "2") (pinfunction "2_2") (pintype "passive"))
      (node (ref "U17") (pin "2") (pinfunction "IN-_2") (pintype "input"))
      (node (ref "U17") (pin "6") (pinfunction "IN-_6") (pintype "input"))
    )
    (net (code "225") (name "VCC3V3") (class "Default")
      (node (ref "C1") (pin "1") (pinfunction "1_1") (pintype "passive"))
      (node (ref "C11") (pin "1") (pinfunction "1_1") (pintype "passive"))
      (node (ref "C14") (pin "1") (pinfunction "1_1") (pintype "passive"))
      (node (ref "C18") (pin "1") (pinfunction "1_1") (pintype "passive"))
      (node (ref "C20") (pin "1") (pinfunction "1_1") (pintype "passive"))
      (node (ref "C26") (pin "1") (pinfunction "1_1") (pintype "passive"))
      (node (ref "C29") (pin "1") (pinfunction "1_1") (pintype "passive"))
      (node (ref "C3") (pin "1") (pinfunction "1_1") (pintype "passive"))
      (node (ref "C30") (pin "1") (pinfunction "1_1") (pintype "passive"))
      (node (ref "C5") (pin "2") (pinfunction "2_2") (pintype "passive"))
      (node (ref "C52") (pin "2") (pinfunction "2_2") (pintype "passive"))
      (node (ref "C54") (pin "2") (pinfunction "2_2") (pintype "passive"))
      (node (ref "C59") (pin "1") (pinfunction "1_1") (pintype "passive"))
      (node (ref "C60") (pin "1") (pinfunction "1_1") (pintype "passive"))
      (node (ref "C9") (pin "1") (pinfunction "1_1") (pintype "passive"))
      (node (ref "DS1") (pin "1") (pinfunction "A_1") (pintype "passive"))
      (node (ref "DS1") (pin "6") (pinfunction "A_6") (pintype "passive"))
      (node (ref "J11") (pin "1") (pinfunction "1_1") (pintype "passive"))
      (node (ref "J7") (pin "1") (pinfunction "VTREF_1") (pintype "passive"))
      (node (ref "J7") (pin "2") (pinfunction "VSS_2") (pintype "passive"))
      (node (ref "R1") (pin "1") (pinfunction "1_1") (pintype "passive"))
      (node (ref "R13") (pin "2") (pinfunction "2_2") (pintype "passive"))
      (node (ref "R15") (pin "1") (pinfunction "1_1") (pintype "passive"))
      (node (ref "R17") (pin "1") (pinfunction "1_1") (pintype "passive"))
      (node (ref "R18") (pin "1") (pinfunction "1_1") (pintype "passive"))
      (node (ref "R19") (pin "1") (pinfunction "1_1") (pintype "passive"))
      (node (ref "R2") (pin "1") (pinfunction "1_1") (pintype "passive"))
      (node (ref "R20") (pin "1") (pinfunction "1_1") (pintype "passive"))
      (node (ref "R21") (pin "1") (pinfunction "1_1") (pintype "passive"))
      (node (ref "R22") (pin "1") (pinfunction "1_1") (pintype "passive"))
      (node (ref "R3") (pin "1") (pinfunction "1_1") (pintype "passive"))
      (node (ref "R4") (pin "1") (pinfunction "1_1") (pintype "passive"))
      (node (ref "R5") (pin "1") (pinfunction "1_1") (pintype "passive"))
      (node (ref "R57") (pin "2") (pinfunction "2_2") (pintype "passive"))
      (node (ref "R6") (pin "1") (pinfunction "1_1") (pintype "passive"))
      (node (ref "R7") (pin "1") (pinfunction "1_1") (pintype "passive"))
      (node (ref "R8") (pin "1") (pinfunction "1_1") (pintype "passive"))
      (node (ref "U1") (pin "4") (pinfunction "VCC_4") (pintype "passive"))
      (node (ref "U11") (pin "16") (pinfunction "VCC_16") (pintype "passive"))
      (node (ref "U12") (pin "16") (pinfunction "VCC_16") (pintype "passive"))
      (node (ref "U3") (pin "8") (pinfunction "VCC_8") (pintype "passive"))
      (node (ref "U5") (pin "100") (pinfunction "VDD_3_100") (pintype "passive"))
      (node (ref "U5") (pin "11") (pinfunction "VDD_5_11") (pintype "passive"))
      (node (ref "U5") (pin "21") (pinfunction "VREF+_21") (pintype "passive"))
      (node (ref "U5") (pin "22") (pinfunction "VDDA_22") (pintype "passive"))
      (node (ref "U5") (pin "28") (pinfunction "VDD_4_28") (pintype "passive"))
      (node (ref "U5") (pin "50") (pinfunction "VDD_1_50") (pintype "passive"))
      (node (ref "U5") (pin "6") (pinfunction "VBAT_6") (pintype "passive"))
      (node (ref "U5") (pin "75") (pinfunction "VDD_2_75") (pintype "passive"))
      (node (ref "U6") (pin "2") (pinfunction "Vout_2") (pintype "passive"))
      (node (ref "U6") (pin "4") (pinfunction "4_4") (pintype "passive"))
      (node (ref "U7") (pin "3") (pinfunction "WP#_3") (pintype "passive"))
      (node (ref "U7") (pin "7") (pinfunction "HOLD_7") (pintype "passive"))
      (node (ref "U7") (pin "8") (pinfunction "VCC_8") (pintype "passive"))
    )
    (net (code "226") (name "unconnected-(J7-DBGACK-Pad19)") (class "Default")
      (node (ref "J7") (pin "19") (pinfunction "DBGACK_19") (pintype "passive"))
    )
    (net (code "227") (name "unconnected-(J7-DBGRQ-Pad17)") (class "Default")
      (node (ref "J7") (pin "17") (pinfunction "DBGRQ_17") (pintype "passive"))
    )
    (net (code "228") (name "unconnected-(J7-RTCK-Pad11)") (class "Default")
      (node (ref "J7") (pin "11") (pinfunction "RTCK_11") (pintype "passive"))
    )
    (net (code "229") (name "unconnected-(J11-Pad13)") (class "Default")
      (node (ref "J11") (pin "13") (pinfunction "13_13") (pintype "passive"))
    )
    (net (code "230") (name "unconnected-(J11-Pad14)") (class "Default")
      (node (ref "J11") (pin "14") (pinfunction "14_14") (pintype "passive"))
    )
    (net (code "231") (name "unconnected-(U1-NC-Pad1)") (class "Default")
      (node (ref "U1") (pin "1") (pinfunction "NC_1") (pintype "passive"))
    )
    (net (code "232") (name "unconnected-(U5-NC-Pad73)") (class "Default")
      (node (ref "U5") (pin "73") (pinfunction "NC_73") (pintype "passive"))
    )
    (net (code "233") (name "unconnected-(U5-OSC_OUT-Pad13)") (class "Default")
      (node (ref "U5") (pin "13") (pinfunction "OSC_OUT_13") (pintype "passive"))
    )
    (net (code "234") (name "unconnected-(U8-D-Pad2)") (class "Default")
      (node (ref "U8") (pin "2") (pinfunction "D_2") (pintype "passive"))
    )
    (net (code "235") (name "unconnected-(U9-COM-Pad9)") (class "Default")
      (node (ref "U9") (pin "9") (pinfunction "COM_9") (pintype "passive"))
    )
    (net (code "236") (name "unconnected-(U12-R1IN-Pad13)") (class "Default")
      (node (ref "U12") (pin "13") (pinfunction "R1IN_13") (pintype "passive"))
    )
    (net (code "237") (name "unconnected-(U12-R1OUT-Pad12)") (class "Default")
      (node (ref "U12") (pin "12") (pinfunction "R1OUT_12") (pintype "passive"))
    )
    (net (code "238") (name "unconnected-(U12-T1IN-Pad11)") (class "Default")
      (node (ref "U12") (pin "11") (pinfunction "T1IN_11") (pintype "passive"))
    )
    (net (code "239") (name "unconnected-(U12-T1OUT-Pad14)") (class "Default")
      (node (ref "U12") (pin "14") (pinfunction "T1OUT_14") (pintype "passive"))
    )
  )
)
